# UCC28740DR_Flyback_converter_SCH.net
KiCad netlist of a schematic drawn in Altium Designer
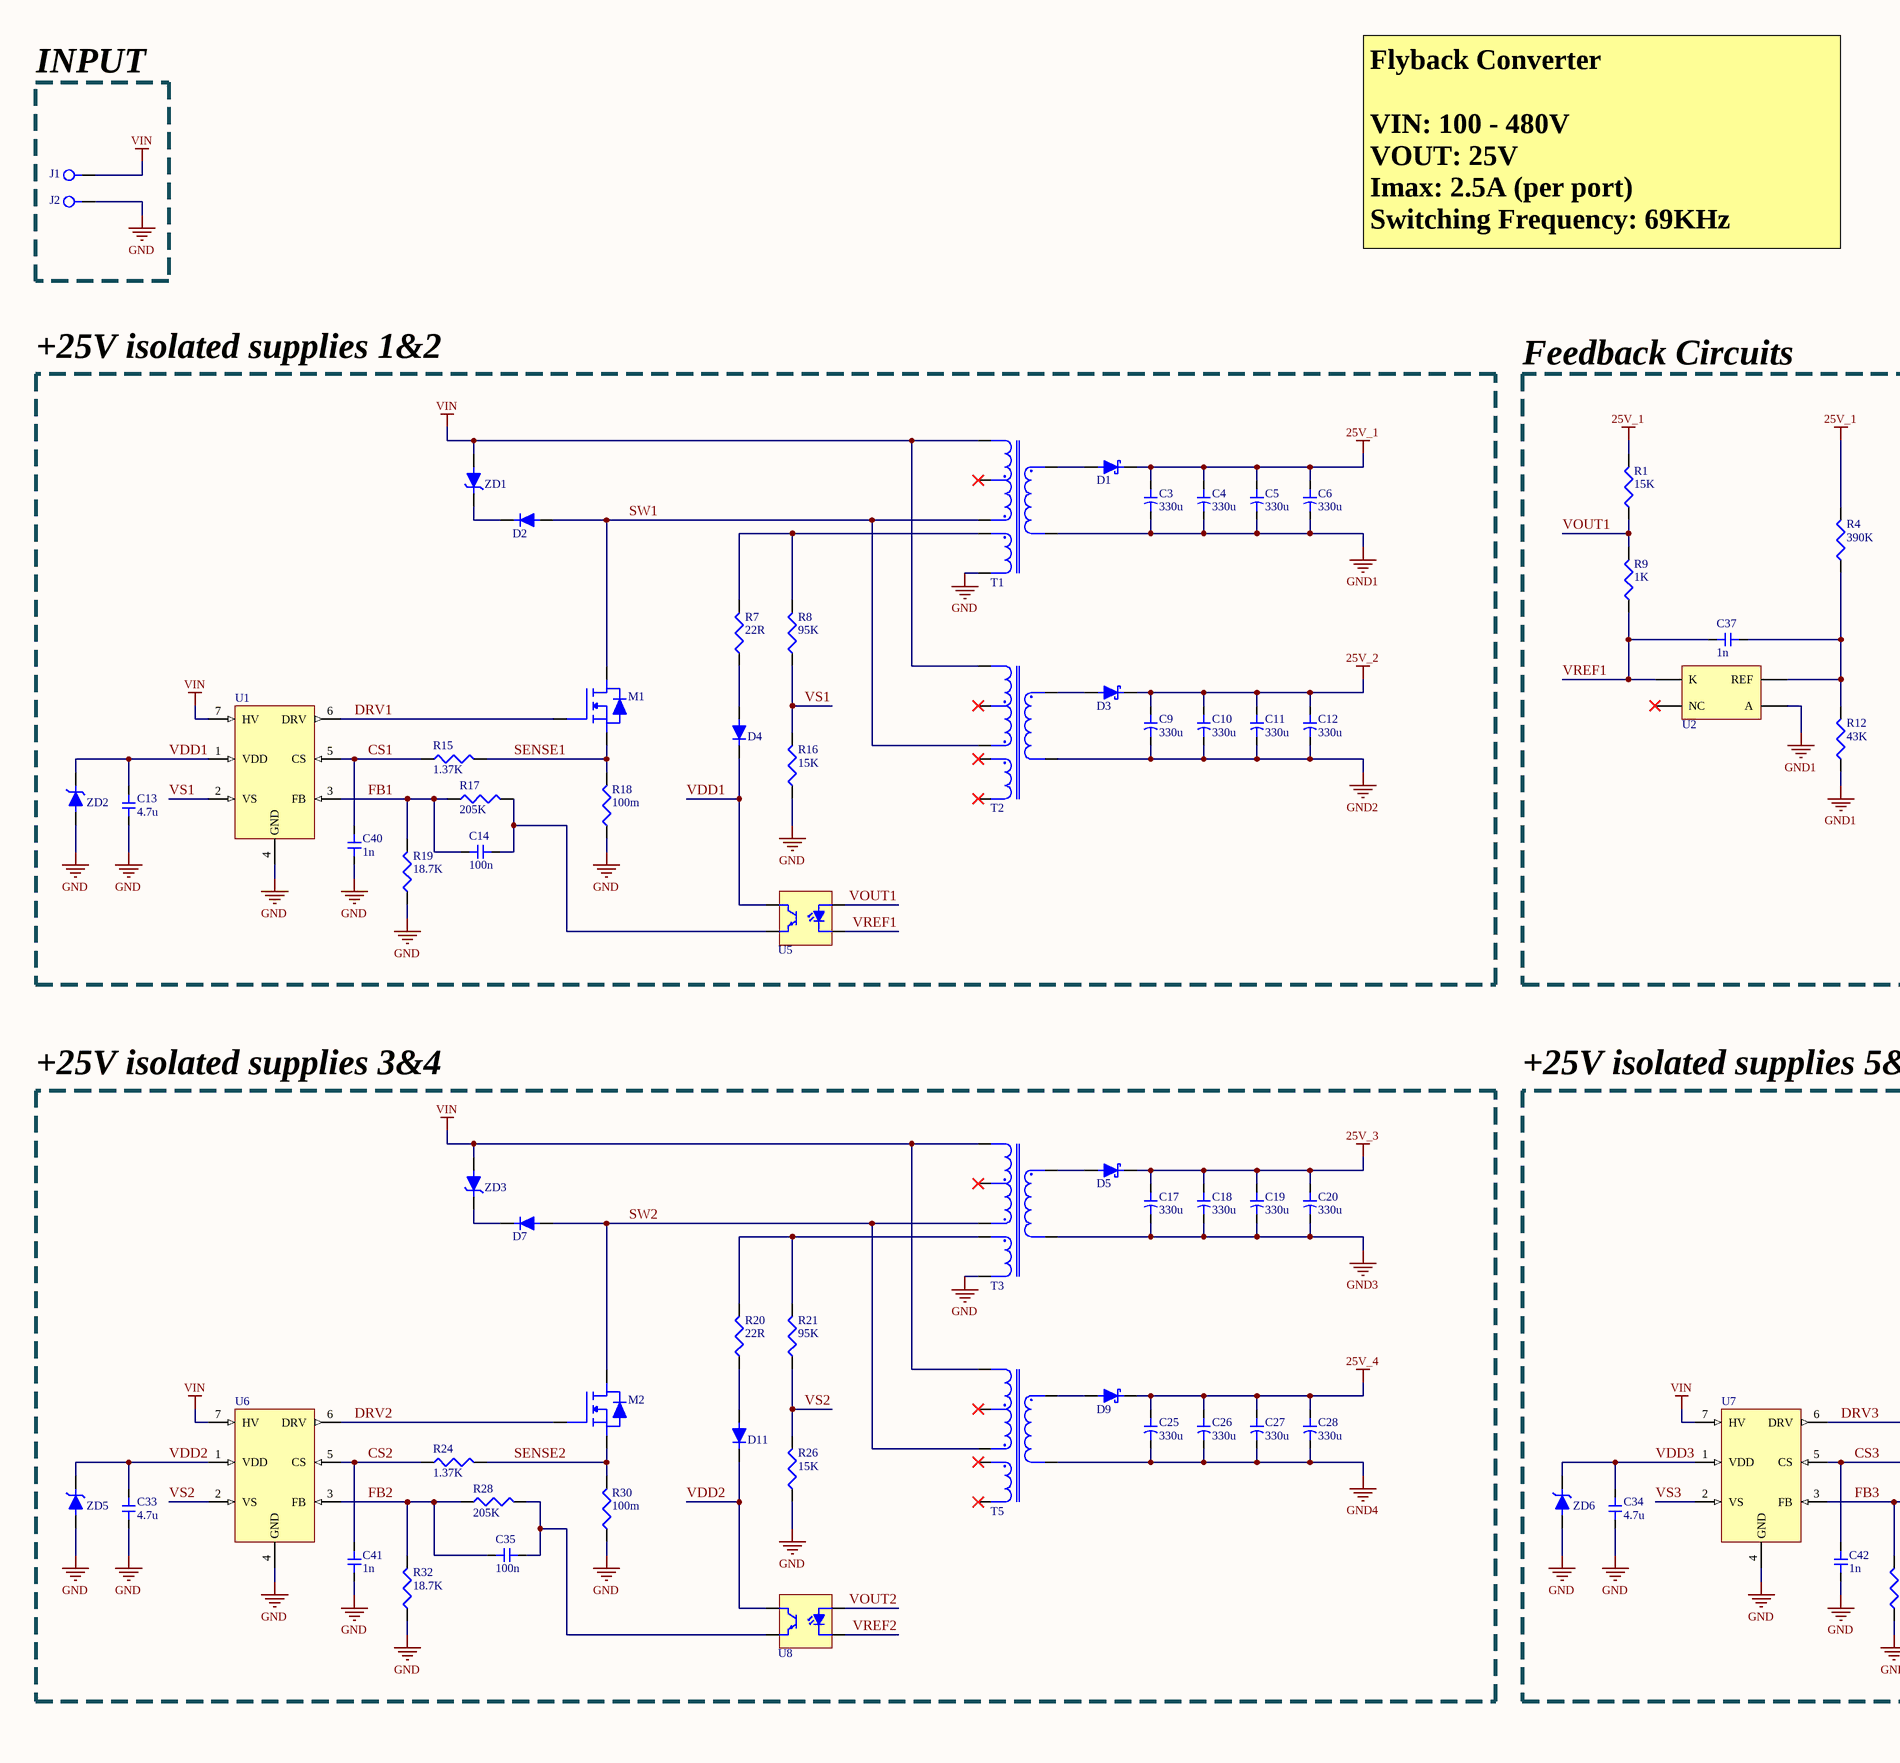
[diagram p0: UCC28740DR Flyback converter SCH.SchDoc, left]
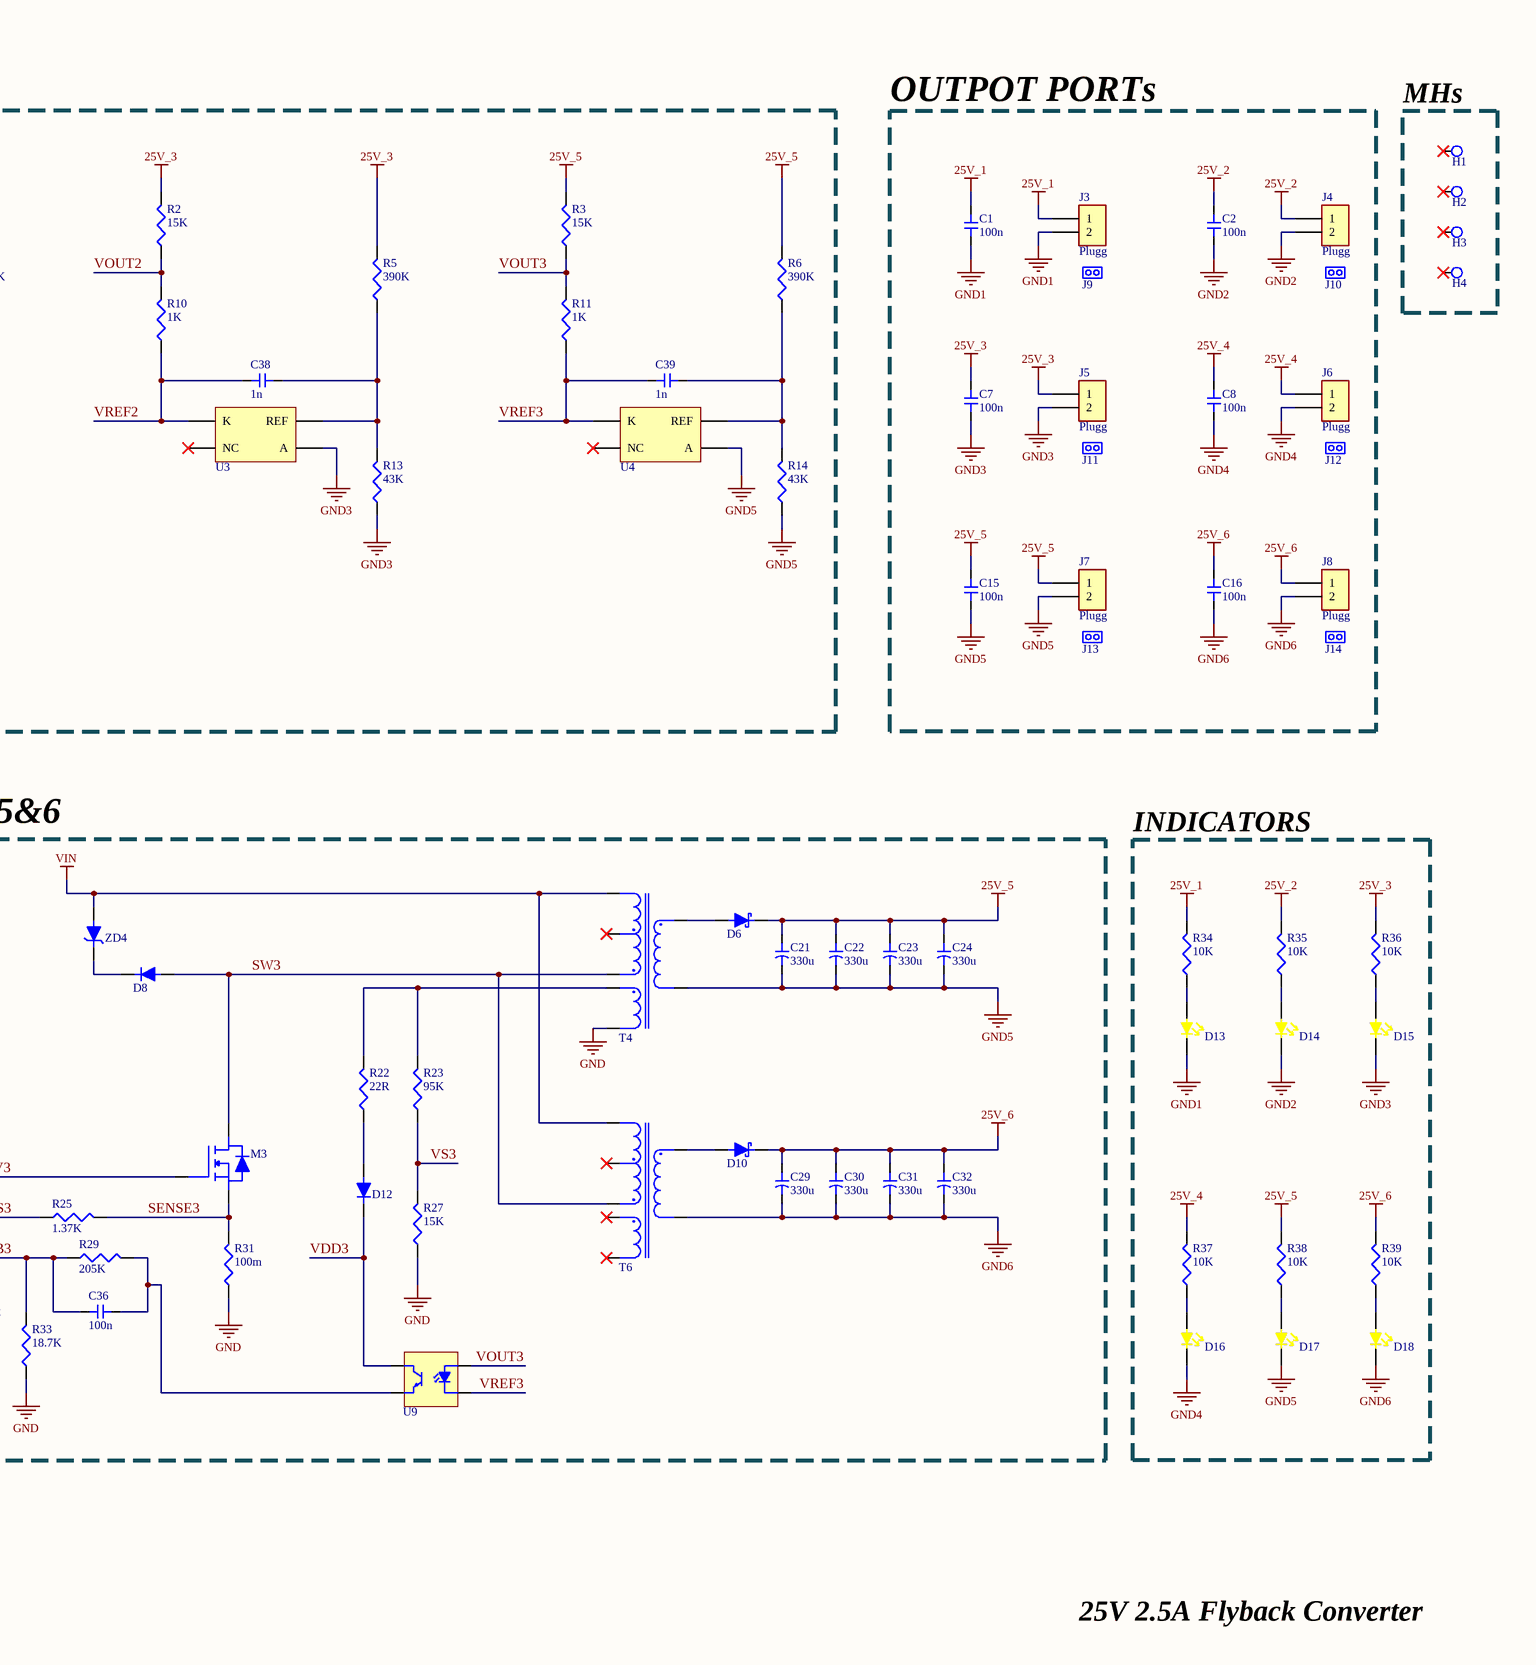
[diagram p1: UCC28740DR Flyback converter SCH.SchDoc, right]

(export (version "E")
  (design (tool "Eeschema 10.0.6"))
  (components
    (comp (ref "C1")
      (value "100n")
      (footprint "0603-CAP")
      (description "50V 100nF X7R ±10% 0603 Multilayer Ceramic Capacitors MLCC - SMD/SMT ROHS")
      (fields (field (name "MANUFACTURER") "YAGEO") (field (name "MFR. PART #") "CC0603KRX7R9BB104"))
      (libsource (lib "Symbols") (part "Cap 100nF"))
    )
    (comp (ref "C2")
      (value "100n")
      (footprint "0603-CAP")
      (description "50V 100nF X7R ±10% 0603 Multilayer Ceramic Capacitors MLCC - SMD/SMT ROHS")
      (fields (field (name "MANUFACTURER") "YAGEO") (field (name "MFR. PART #") "CC0603KRX7R9BB104"))
      (libsource (lib "Symbols") (part "Cap 100nF"))
    )
    (comp (ref "C3")
      (value "330u")
      (footprint "Electrolytic Capacitor D13 P5 H25")
      (description "330uF 100V Plugin,D13xL26mm Aluminum Electrolytic Capacitors - Leaded ROHS")
      (fields (field (name "MANUFACTURER") "HRK") (field (name "MFR. PART #") "CD2883372AM1326VFL"))
      (libsource (lib "Symbols") (part "Electrolytic Cap 330u"))
    )
    (comp (ref "C4")
      (value "330u")
      (footprint "Electrolytic Capacitor D13 P5 H25")
      (description "330uF 100V Plugin,D13xL26mm Aluminum Electrolytic Capacitors - Leaded ROHS")
      (fields (field (name "MANUFACTURER") "HRK") (field (name "MFR. PART #") "CD2883372AM1326VFL"))
      (libsource (lib "Symbols") (part "Electrolytic Cap 330u"))
    )
    (comp (ref "C5")
      (value "330u")
      (footprint "Electrolytic Capacitor D13 P5 H25")
      (description "330uF 100V Plugin,D13xL26mm Aluminum Electrolytic Capacitors - Leaded ROHS")
      (fields (field (name "MANUFACTURER") "HRK") (field (name "MFR. PART #") "CD2883372AM1326VFL"))
      (libsource (lib "Symbols") (part "Electrolytic Cap 330u"))
    )
    (comp (ref "C6")
      (value "330u")
      (footprint "Electrolytic Capacitor D13 P5 H25")
      (description "330uF 100V Plugin,D13xL26mm Aluminum Electrolytic Capacitors - Leaded ROHS")
      (fields (field (name "MANUFACTURER") "HRK") (field (name "MFR. PART #") "CD2883372AM1326VFL"))
      (libsource (lib "Symbols") (part "Electrolytic Cap 330u"))
    )
    (comp (ref "C7")
      (value "100n")
      (footprint "0603-CAP")
      (description "50V 100nF X7R ±10% 0603 Multilayer Ceramic Capacitors MLCC - SMD/SMT ROHS")
      (fields (field (name "MANUFACTURER") "YAGEO") (field (name "MFR. PART #") "CC0603KRX7R9BB104"))
      (libsource (lib "Symbols") (part "Cap 100nF"))
    )
    (comp (ref "C8")
      (value "100n")
      (footprint "0603-CAP")
      (description "50V 100nF X7R ±10% 0603 Multilayer Ceramic Capacitors MLCC - SMD/SMT ROHS")
      (fields (field (name "MANUFACTURER") "YAGEO") (field (name "MFR. PART #") "CC0603KRX7R9BB104"))
      (libsource (lib "Symbols") (part "Cap 100nF"))
    )
    (comp (ref "C9")
      (value "330u")
      (footprint "Electrolytic Capacitor D13 P5 H25")
      (description "330uF 100V Plugin,D13xL26mm Aluminum Electrolytic Capacitors - Leaded ROHS")
      (fields (field (name "MANUFACTURER") "HRK") (field (name "MFR. PART #") "CD2883372AM1326VFL"))
      (libsource (lib "Symbols") (part "Electrolytic Cap 330u"))
    )
    (comp (ref "C10")
      (value "330u")
      (footprint "Electrolytic Capacitor D13 P5 H25")
      (description "330uF 100V Plugin,D13xL26mm Aluminum Electrolytic Capacitors - Leaded ROHS")
      (fields (field (name "MANUFACTURER") "HRK") (field (name "MFR. PART #") "CD2883372AM1326VFL"))
      (libsource (lib "Symbols") (part "Electrolytic Cap 330u"))
    )
    (comp (ref "C11")
      (value "330u")
      (footprint "Electrolytic Capacitor D13 P5 H25")
      (description "330uF 100V Plugin,D13xL26mm Aluminum Electrolytic Capacitors - Leaded ROHS")
      (fields (field (name "MANUFACTURER") "HRK") (field (name "MFR. PART #") "CD2883372AM1326VFL"))
      (libsource (lib "Symbols") (part "Electrolytic Cap 330u"))
    )
    (comp (ref "C12")
      (value "330u")
      (footprint "Electrolytic Capacitor D13 P5 H25")
      (description "330uF 100V Plugin,D13xL26mm Aluminum Electrolytic Capacitors - Leaded ROHS")
      (fields (field (name "MANUFACTURER") "HRK") (field (name "MFR. PART #") "CD2883372AM1326VFL"))
      (libsource (lib "Symbols") (part "Electrolytic Cap 330u"))
    )
    (comp (ref "C13")
      (value "4.7u")
      (footprint "0805-CAP")
      (description "50V 4.7uF X7R ±10% 0805 Multilayer Ceramic Capacitors MLCC - SMD/SMT ROHS")
      (fields
        (field (name "MANUFACTURER") "FH (Guangdong Fenghua Advanced Tech)")
        (field (name "MFR. PART #") "0805B475K500NT")
      )
      (libsource (lib "Symbols") (part "Cap 4.7uF"))
    )
    (comp (ref "C14")
      (value "100n")
      (footprint "0603-CAP")
      (description "50V 100nF X7R ±10% 0603 Multilayer Ceramic Capacitors MLCC - SMD/SMT ROHS")
      (fields (field (name "MANUFACTURER") "YAGEO") (field (name "MFR. PART #") "CC0603KRX7R9BB104"))
      (libsource (lib "Symbols") (part "Cap 100nF"))
    )
    (comp (ref "C15")
      (value "100n")
      (footprint "0603-CAP")
      (description "50V 100nF X7R ±10% 0603 Multilayer Ceramic Capacitors MLCC - SMD/SMT ROHS")
      (fields (field (name "MANUFACTURER") "YAGEO") (field (name "MFR. PART #") "CC0603KRX7R9BB104"))
      (libsource (lib "Symbols") (part "Cap 100nF"))
    )
    (comp (ref "C16")
      (value "100n")
      (footprint "0603-CAP")
      (description "50V 100nF X7R ±10% 0603 Multilayer Ceramic Capacitors MLCC - SMD/SMT ROHS")
      (fields (field (name "MANUFACTURER") "YAGEO") (field (name "MFR. PART #") "CC0603KRX7R9BB104"))
      (libsource (lib "Symbols") (part "Cap 100nF"))
    )
    (comp (ref "C17")
      (value "330u")
      (footprint "Electrolytic Capacitor D13 P5 H25")
      (description "330uF 100V Plugin,D13xL26mm Aluminum Electrolytic Capacitors - Leaded ROHS")
      (fields (field (name "MANUFACTURER") "HRK") (field (name "MFR. PART #") "CD2883372AM1326VFL"))
      (libsource (lib "Symbols") (part "Electrolytic Cap 330u"))
    )
    (comp (ref "C18")
      (value "330u")
      (footprint "Electrolytic Capacitor D13 P5 H25")
      (description "330uF 100V Plugin,D13xL26mm Aluminum Electrolytic Capacitors - Leaded ROHS")
      (fields (field (name "MANUFACTURER") "HRK") (field (name "MFR. PART #") "CD2883372AM1326VFL"))
      (libsource (lib "Symbols") (part "Electrolytic Cap 330u"))
    )
    (comp (ref "C19")
      (value "330u")
      (footprint "Electrolytic Capacitor D13 P5 H25")
      (description "330uF 100V Plugin,D13xL26mm Aluminum Electrolytic Capacitors - Leaded ROHS")
      (fields (field (name "MANUFACTURER") "HRK") (field (name "MFR. PART #") "CD2883372AM1326VFL"))
      (libsource (lib "Symbols") (part "Electrolytic Cap 330u"))
    )
    (comp (ref "C20")
      (value "330u")
      (footprint "Electrolytic Capacitor D13 P5 H25")
      (description "330uF 100V Plugin,D13xL26mm Aluminum Electrolytic Capacitors - Leaded ROHS")
      (fields (field (name "MANUFACTURER") "HRK") (field (name "MFR. PART #") "CD2883372AM1326VFL"))
      (libsource (lib "Symbols") (part "Electrolytic Cap 330u"))
    )
    (comp (ref "C21")
      (value "330u")
      (footprint "Electrolytic Capacitor D13 P5 H25")
      (description "330uF 100V Plugin,D13xL26mm Aluminum Electrolytic Capacitors - Leaded ROHS")
      (fields (field (name "MANUFACTURER") "HRK") (field (name "MFR. PART #") "CD2883372AM1326VFL"))
      (libsource (lib "Symbols") (part "Electrolytic Cap 330u"))
    )
    (comp (ref "C22")
      (value "330u")
      (footprint "Electrolytic Capacitor D13 P5 H25")
      (description "330uF 100V Plugin,D13xL26mm Aluminum Electrolytic Capacitors - Leaded ROHS")
      (fields (field (name "MANUFACTURER") "HRK") (field (name "MFR. PART #") "CD2883372AM1326VFL"))
      (libsource (lib "Symbols") (part "Electrolytic Cap 330u"))
    )
    (comp (ref "C23")
      (value "330u")
      (footprint "Electrolytic Capacitor D13 P5 H25")
      (description "330uF 100V Plugin,D13xL26mm Aluminum Electrolytic Capacitors - Leaded ROHS")
      (fields (field (name "MANUFACTURER") "HRK") (field (name "MFR. PART #") "CD2883372AM1326VFL"))
      (libsource (lib "Symbols") (part "Electrolytic Cap 330u"))
    )
    (comp (ref "C24")
      (value "330u")
      (footprint "Electrolytic Capacitor D13 P5 H25")
      (description "330uF 100V Plugin,D13xL26mm Aluminum Electrolytic Capacitors - Leaded ROHS")
      (fields (field (name "MANUFACTURER") "HRK") (field (name "MFR. PART #") "CD2883372AM1326VFL"))
      (libsource (lib "Symbols") (part "Electrolytic Cap 330u"))
    )
    (comp (ref "C25")
      (value "330u")
      (footprint "Electrolytic Capacitor D13 P5 H25")
      (description "330uF 100V Plugin,D13xL26mm Aluminum Electrolytic Capacitors - Leaded ROHS")
      (fields (field (name "MANUFACTURER") "HRK") (field (name "MFR. PART #") "CD2883372AM1326VFL"))
      (libsource (lib "Symbols") (part "Electrolytic Cap 330u"))
    )
    (comp (ref "C26")
      (value "330u")
      (footprint "Electrolytic Capacitor D13 P5 H25")
      (description "330uF 100V Plugin,D13xL26mm Aluminum Electrolytic Capacitors - Leaded ROHS")
      (fields (field (name "MANUFACTURER") "HRK") (field (name "MFR. PART #") "CD2883372AM1326VFL"))
      (libsource (lib "Symbols") (part "Electrolytic Cap 330u"))
    )
    (comp (ref "C27")
      (value "330u")
      (footprint "Electrolytic Capacitor D13 P5 H25")
      (description "330uF 100V Plugin,D13xL26mm Aluminum Electrolytic Capacitors - Leaded ROHS")
      (fields (field (name "MANUFACTURER") "HRK") (field (name "MFR. PART #") "CD2883372AM1326VFL"))
      (libsource (lib "Symbols") (part "Electrolytic Cap 330u"))
    )
    (comp (ref "C28")
      (value "330u")
      (footprint "Electrolytic Capacitor D13 P5 H25")
      (description "330uF 100V Plugin,D13xL26mm Aluminum Electrolytic Capacitors - Leaded ROHS")
      (fields (field (name "MANUFACTURER") "HRK") (field (name "MFR. PART #") "CD2883372AM1326VFL"))
      (libsource (lib "Symbols") (part "Electrolytic Cap 330u"))
    )
    (comp (ref "C29")
      (value "330u")
      (footprint "Electrolytic Capacitor D13 P5 H25")
      (description "330uF 100V Plugin,D13xL26mm Aluminum Electrolytic Capacitors - Leaded ROHS")
      (fields (field (name "MANUFACTURER") "HRK") (field (name "MFR. PART #") "CD2883372AM1326VFL"))
      (libsource (lib "Symbols") (part "Electrolytic Cap 330u"))
    )
    (comp (ref "C30")
      (value "330u")
      (footprint "Electrolytic Capacitor D13 P5 H25")
      (description "330uF 100V Plugin,D13xL26mm Aluminum Electrolytic Capacitors - Leaded ROHS")
      (fields (field (name "MANUFACTURER") "HRK") (field (name "MFR. PART #") "CD2883372AM1326VFL"))
      (libsource (lib "Symbols") (part "Electrolytic Cap 330u"))
    )
    (comp (ref "C31")
      (value "330u")
      (footprint "Electrolytic Capacitor D13 P5 H25")
      (description "330uF 100V Plugin,D13xL26mm Aluminum Electrolytic Capacitors - Leaded ROHS")
      (fields (field (name "MANUFACTURER") "HRK") (field (name "MFR. PART #") "CD2883372AM1326VFL"))
      (libsource (lib "Symbols") (part "Electrolytic Cap 330u"))
    )
    (comp (ref "C32")
      (value "330u")
      (footprint "Electrolytic Capacitor D13 P5 H25")
      (description "330uF 100V Plugin,D13xL26mm Aluminum Electrolytic Capacitors - Leaded ROHS")
      (fields (field (name "MANUFACTURER") "HRK") (field (name "MFR. PART #") "CD2883372AM1326VFL"))
      (libsource (lib "Symbols") (part "Electrolytic Cap 330u"))
    )
    (comp (ref "C33")
      (value "4.7u")
      (footprint "0805-CAP")
      (description "50V 4.7uF X7R ±10% 0805 Multilayer Ceramic Capacitors MLCC - SMD/SMT ROHS")
      (fields
        (field (name "MANUFACTURER") "FH (Guangdong Fenghua Advanced Tech)")
        (field (name "MFR. PART #") "0805B475K500NT")
      )
      (libsource (lib "Symbols") (part "Cap 4.7uF"))
    )
    (comp (ref "C34")
      (value "4.7u")
      (footprint "0805-CAP")
      (description "50V 4.7uF X7R ±10% 0805 Multilayer Ceramic Capacitors MLCC - SMD/SMT ROHS")
      (fields
        (field (name "MANUFACTURER") "FH (Guangdong Fenghua Advanced Tech)")
        (field (name "MFR. PART #") "0805B475K500NT")
      )
      (libsource (lib "Symbols") (part "Cap 4.7uF"))
    )
    (comp (ref "C35")
      (value "100n")
      (footprint "0603-CAP")
      (description "50V 100nF X7R ±10% 0603 Multilayer Ceramic Capacitors MLCC - SMD/SMT ROHS")
      (fields (field (name "MANUFACTURER") "YAGEO") (field (name "MFR. PART #") "CC0603KRX7R9BB104"))
      (libsource (lib "Symbols") (part "Cap 100nF"))
    )
    (comp (ref "C36")
      (value "100n")
      (footprint "0603-CAP")
      (description "50V 100nF X7R ±10% 0603 Multilayer Ceramic Capacitors MLCC - SMD/SMT ROHS")
      (fields (field (name "MANUFACTURER") "YAGEO") (field (name "MFR. PART #") "CC0603KRX7R9BB104"))
      (libsource (lib "Symbols") (part "Cap 100nF"))
    )
    (comp (ref "C37")
      (value "1n")
      (footprint "0603-CAP")
      (description "50V 1nF X7R ±10% 0603 Multilayer Ceramic Capacitors MLCC - SMD/SMT ROHS")
      (fields (field (name "MANUFACTURER") "YAGEO") (field (name "MFR. PART #") "CC0603KRX7R9BB102"))
      (libsource (lib "Symbols") (part "Cap 1nF"))
    )
    (comp (ref "C38")
      (value "1n")
      (footprint "0603-CAP")
      (description "50V 1nF X7R ±10% 0603 Multilayer Ceramic Capacitors MLCC - SMD/SMT ROHS")
      (fields (field (name "MANUFACTURER") "YAGEO") (field (name "MFR. PART #") "CC0603KRX7R9BB102"))
      (libsource (lib "Symbols") (part "Cap 1nF"))
    )
    (comp (ref "C39")
      (value "1n")
      (footprint "0603-CAP")
      (description "50V 1nF X7R ±10% 0603 Multilayer Ceramic Capacitors MLCC - SMD/SMT ROHS")
      (fields (field (name "MANUFACTURER") "YAGEO") (field (name "MFR. PART #") "CC0603KRX7R9BB102"))
      (libsource (lib "Symbols") (part "Cap 1nF"))
    )
    (comp (ref "C40")
      (value "1n")
      (footprint "0603-CAP")
      (description "50V 1nF X7R ±10% 0603 Multilayer Ceramic Capacitors MLCC - SMD/SMT ROHS")
      (fields (field (name "MANUFACTURER") "YAGEO") (field (name "MFR. PART #") "CC0603KRX7R9BB102"))
      (libsource (lib "Symbols") (part "Cap 1nF"))
    )
    (comp (ref "C41")
      (value "1n")
      (footprint "0603-CAP")
      (description "50V 1nF X7R ±10% 0603 Multilayer Ceramic Capacitors MLCC - SMD/SMT ROHS")
      (fields (field (name "MANUFACTURER") "YAGEO") (field (name "MFR. PART #") "CC0603KRX7R9BB102"))
      (libsource (lib "Symbols") (part "Cap 1nF"))
    )
    (comp (ref "C42")
      (value "1n")
      (footprint "0603-CAP")
      (description "50V 1nF X7R ±10% 0603 Multilayer Ceramic Capacitors MLCC - SMD/SMT ROHS")
      (fields (field (name "MANUFACTURER") "YAGEO") (field (name "MFR. PART #") "CC0603KRX7R9BB102"))
      (libsource (lib "Symbols") (part "Cap 1nF"))
    )
    (comp (ref "D1")
      (value "Schottky Diode")
      (footprint "SMA(DO-214AC)")
      (description "100V Independent Type 850mV@5A 5A SMA(DO-214AC) Schottky Diodes ROHS")
      (fields (field (name "MANUFACTURER") "TWGMC") (field (name "MFR. PART #") "SS510"))
      (libsource (lib "Symbols") (part "Schottky Diode"))
    )
    (comp (ref "D2")
      (value "Fast Diode")
      (footprint "SMC diode")
      (description "1.7V@8A 80ns Independent Type 8A 1kV SMC Fast Recovery / High Efficiency Diodes ROHS")
      (fields
        (field (name "MANUFACTURER") "Shandong Jingdao Microelectronics")
        (field (name "MFR. PART #") "US8MC")
      )
      (libsource (lib "Symbols") (part "Fast Diode"))
    )
    (comp (ref "D3")
      (value "Schottky Diode")
      (footprint "SMA(DO-214AC)")
      (description "100V Independent Type 850mV@5A 5A SMA(DO-214AC) Schottky Diodes ROHS")
      (fields (field (name "MANUFACTURER") "TWGMC") (field (name "MFR. PART #") "SS510"))
      (libsource (lib "Symbols") (part "Schottky Diode"))
    )
    (comp (ref "D4")
      (value "Fast Diode")
      (footprint "SMC diode")
      (description "1.7V@8A 80ns Independent Type 8A 1kV SMC Fast Recovery / High Efficiency Diodes ROHS")
      (fields
        (field (name "MANUFACTURER") "Shandong Jingdao Microelectronics")
        (field (name "MFR. PART #") "US8MC")
      )
      (libsource (lib "Symbols") (part "Fast Diode"))
    )
    (comp (ref "D5")
      (value "Schottky Diode")
      (footprint "SMA(DO-214AC)")
      (description "100V Independent Type 850mV@5A 5A SMA(DO-214AC) Schottky Diodes ROHS")
      (fields (field (name "MANUFACTURER") "TWGMC") (field (name "MFR. PART #") "SS510"))
      (libsource (lib "Symbols") (part "Schottky Diode"))
    )
    (comp (ref "D6")
      (value "Schottky Diode")
      (footprint "SMA(DO-214AC)")
      (description "100V Independent Type 850mV@5A 5A SMA(DO-214AC) Schottky Diodes ROHS")
      (fields (field (name "MANUFACTURER") "TWGMC") (field (name "MFR. PART #") "SS510"))
      (libsource (lib "Symbols") (part "Schottky Diode"))
    )
    (comp (ref "D7")
      (value "Fast Diode")
      (footprint "SMC diode")
      (description "1.7V@8A 80ns Independent Type 8A 1kV SMC Fast Recovery / High Efficiency Diodes ROHS")
      (fields
        (field (name "MANUFACTURER") "Shandong Jingdao Microelectronics")
        (field (name "MFR. PART #") "US8MC")
      )
      (libsource (lib "Symbols") (part "Fast Diode"))
    )
    (comp (ref "D8")
      (value "Fast Diode")
      (footprint "SMC diode")
      (description "1.7V@8A 80ns Independent Type 8A 1kV SMC Fast Recovery / High Efficiency Diodes ROHS")
      (fields
        (field (name "MANUFACTURER") "Shandong Jingdao Microelectronics")
        (field (name "MFR. PART #") "US8MC")
      )
      (libsource (lib "Symbols") (part "Fast Diode"))
    )
    (comp (ref "D9")
      (value "Schottky Diode")
      (footprint "SMA(DO-214AC)")
      (description "100V Independent Type 850mV@5A 5A SMA(DO-214AC) Schottky Diodes ROHS")
      (fields (field (name "MANUFACTURER") "TWGMC") (field (name "MFR. PART #") "SS510"))
      (libsource (lib "Symbols") (part "Schottky Diode"))
    )
    (comp (ref "D10")
      (value "Schottky Diode")
      (footprint "SMA(DO-214AC)")
      (description "100V Independent Type 850mV@5A 5A SMA(DO-214AC) Schottky Diodes ROHS")
      (fields (field (name "MANUFACTURER") "TWGMC") (field (name "MFR. PART #") "SS510"))
      (libsource (lib "Symbols") (part "Schottky Diode"))
    )
    (comp (ref "D11")
      (value "Fast Diode")
      (footprint "SMC diode")
      (description "1.7V@8A 80ns Independent Type 8A 1kV SMC Fast Recovery / High Efficiency Diodes ROHS")
      (fields
        (field (name "MANUFACTURER") "Shandong Jingdao Microelectronics")
        (field (name "MFR. PART #") "US8MC")
      )
      (libsource (lib "Symbols") (part "Fast Diode"))
    )
    (comp (ref "D12")
      (value "Fast Diode")
      (footprint "SMC diode")
      (description "1.7V@8A 80ns Independent Type 8A 1kV SMC Fast Recovery / High Efficiency Diodes ROHS")
      (fields
        (field (name "MANUFACTURER") "Shandong Jingdao Microelectronics")
        (field (name "MFR. PART #") "US8MC")
      )
      (libsource (lib "Symbols") (part "Fast Diode"))
    )
    (comp (ref "D13")
      (value "Yellow LED")
      (footprint "yellow led")
      (description "2-Yellow lens-30℃~+85℃ Positive post White 120° 80mW 0805 Light Emitting Diodes (LED) ROHS")
      (fields (field (name "MANUFACTURER") "XINGLIGHT") (field (name "MFR. PART #") "XL-2012UWC"))
      (libsource (lib "Symbols") (part "Yellow LED"))
    )
    (comp (ref "D14")
      (value "Yellow LED")
      (footprint "yellow led")
      (description "2-Yellow lens-30℃~+85℃ Positive post White 120° 80mW 0805 Light Emitting Diodes (LED) ROHS")
      (fields (field (name "MANUFACTURER") "XINGLIGHT") (field (name "MFR. PART #") "XL-2012UWC"))
      (libsource (lib "Symbols") (part "Yellow LED"))
    )
    (comp (ref "D15")
      (value "Yellow LED")
      (footprint "yellow led")
      (description "2-Yellow lens-30℃~+85℃ Positive post White 120° 80mW 0805 Light Emitting Diodes (LED) ROHS")
      (fields (field (name "MANUFACTURER") "XINGLIGHT") (field (name "MFR. PART #") "XL-2012UWC"))
      (libsource (lib "Symbols") (part "Yellow LED"))
    )
    (comp (ref "D16")
      (value "Yellow LED")
      (footprint "yellow led")
      (description "2-Yellow lens-30℃~+85℃ Positive post White 120° 80mW 0805 Light Emitting Diodes (LED) ROHS")
      (fields (field (name "MANUFACTURER") "XINGLIGHT") (field (name "MFR. PART #") "XL-2012UWC"))
      (libsource (lib "Symbols") (part "Yellow LED"))
    )
    (comp (ref "D17")
      (value "Yellow LED")
      (footprint "yellow led")
      (description "2-Yellow lens-30℃~+85℃ Positive post White 120° 80mW 0805 Light Emitting Diodes (LED) ROHS")
      (fields (field (name "MANUFACTURER") "XINGLIGHT") (field (name "MFR. PART #") "XL-2012UWC"))
      (libsource (lib "Symbols") (part "Yellow LED"))
    )
    (comp (ref "D18")
      (value "Yellow LED")
      (footprint "yellow led")
      (description "2-Yellow lens-30℃~+85℃ Positive post White 120° 80mW 0805 Light Emitting Diodes (LED) ROHS")
      (fields (field (name "MANUFACTURER") "XINGLIGHT") (field (name "MFR. PART #") "XL-2012UWC"))
      (libsource (lib "Symbols") (part "Yellow LED"))
    )
    (comp (ref "H1")
      (value "Mounting hole")
      (footprint "Monting Hole")
      (libsource (lib "Symbols") (part "Mounting hole"))
    )
    (comp (ref "H2")
      (value "Mounting hole")
      (footprint "Monting Hole")
      (libsource (lib "Symbols") (part "Mounting hole"))
    )
    (comp (ref "H3")
      (value "Mounting hole")
      (footprint "Monting Hole")
      (libsource (lib "Symbols") (part "Mounting hole"))
    )
    (comp (ref "H4")
      (value "Mounting hole")
      (footprint "Monting Hole")
      (libsource (lib "Symbols") (part "Mounting hole"))
    )
    (comp (ref "J1")
      (value "Banana Connector Red")
      (footprint "Bannana Connector Red")
      (description "Terminal Red Banana Connectors / Alligator Clips ROHS")
      (fields (field (name "MANUFACTURER") "Changzhou Amass Elec") (field (name "MFR. PART #") "24.247.1"))
      (libsource (lib "Symbols") (part "Banana Connector Red"))
    )
    (comp (ref "J2")
      (value "Banana Connector Black")
      (footprint "Bannana Connector Black")
      (description "Terminal Black Banana Connectors / Alligator Clips ROHS")
      (fields (field (name "MANUFACTURER") "Changzhou Amass Elec") (field (name "MFR. PART #") "24.247.2"))
      (libsource (lib "Symbols") (part "Banana Connector Black"))
    )
    (comp (ref "J3")
      (value "Plugg")
      (footprint "Pluggable Terminal Block 2")
      (fields
        (field (name "MFR. PART #") "WJ2EDGR-5.08-2P")
        (field (name "MANUFACTURER") "Ningbo Kangnex Elec")
      )
      (libsource (lib "Symbols") (part "Pluggable Rozzeta 2P"))
    )
    (comp (ref "J4")
      (value "Plugg")
      (footprint "Pluggable Terminal Block 2")
      (fields
        (field (name "MFR. PART #") "WJ2EDGR-5.08-2P")
        (field (name "MANUFACTURER") "Ningbo Kangnex Elec")
      )
      (libsource (lib "Symbols") (part "Pluggable Rozzeta 2P"))
    )
    (comp (ref "J5")
      (value "Plugg")
      (footprint "Pluggable Terminal Block 2")
      (fields
        (field (name "MFR. PART #") "WJ2EDGR-5.08-2P")
        (field (name "MANUFACTURER") "Ningbo Kangnex Elec")
      )
      (libsource (lib "Symbols") (part "Pluggable Rozzeta 2P"))
    )
    (comp (ref "J6")
      (value "Plugg")
      (footprint "Pluggable Terminal Block 2")
      (fields
        (field (name "MFR. PART #") "WJ2EDGR-5.08-2P")
        (field (name "MANUFACTURER") "Ningbo Kangnex Elec")
      )
      (libsource (lib "Symbols") (part "Pluggable Rozzeta 2P"))
    )
    (comp (ref "J7")
      (value "Plugg")
      (footprint "Pluggable Terminal Block 2")
      (fields
        (field (name "MFR. PART #") "WJ2EDGR-5.08-2P")
        (field (name "MANUFACTURER") "Ningbo Kangnex Elec")
      )
      (libsource (lib "Symbols") (part "Pluggable Rozzeta 2P"))
    )
    (comp (ref "J8")
      (value "Plugg")
      (footprint "Pluggable Terminal Block 2")
      (fields
        (field (name "MFR. PART #") "WJ2EDGR-5.08-2P")
        (field (name "MANUFACTURER") "Ningbo Kangnex Elec")
      )
      (libsource (lib "Symbols") (part "Pluggable Rozzeta 2P"))
    )
    (comp (ref "J9")
      (value "Pluggable Rozzeta 2P female")
      (fields
        (field (name "MFR. PART #") "WJ2EDGK-5.08-2P")
        (field (name "MANUFACTURER") "Ningbo Kangnex Elec")
      )
      (libsource (lib "Symbols") (part "Pluggable Rozzeta 2P female"))
    )
    (comp (ref "J10")
      (value "Pluggable Rozzeta 2P female")
      (fields
        (field (name "MFR. PART #") "WJ2EDGK-5.08-2P")
        (field (name "MANUFACTURER") "Ningbo Kangnex Elec")
      )
      (libsource (lib "Symbols") (part "Pluggable Rozzeta 2P female"))
    )
    (comp (ref "J11")
      (value "Pluggable Rozzeta 2P female")
      (fields
        (field (name "MFR. PART #") "WJ2EDGK-5.08-2P")
        (field (name "MANUFACTURER") "Ningbo Kangnex Elec")
      )
      (libsource (lib "Symbols") (part "Pluggable Rozzeta 2P female"))
    )
    (comp (ref "J12")
      (value "Pluggable Rozzeta 2P female")
      (fields
        (field (name "MFR. PART #") "WJ2EDGK-5.08-2P")
        (field (name "MANUFACTURER") "Ningbo Kangnex Elec")
      )
      (libsource (lib "Symbols") (part "Pluggable Rozzeta 2P female"))
    )
    (comp (ref "J13")
      (value "Pluggable Rozzeta 2P female")
      (fields
        (field (name "MFR. PART #") "WJ2EDGK-5.08-2P")
        (field (name "MANUFACTURER") "Ningbo Kangnex Elec")
      )
      (libsource (lib "Symbols") (part "Pluggable Rozzeta 2P female"))
    )
    (comp (ref "J14")
      (value "Pluggable Rozzeta 2P female")
      (fields
        (field (name "MFR. PART #") "WJ2EDGK-5.08-2P")
        (field (name "MANUFACTURER") "Ningbo Kangnex Elec")
      )
      (libsource (lib "Symbols") (part "Pluggable Rozzeta 2P female"))
    )
    (comp (ref "M1")
      (value "650V 20A MOSFET")
      (footprint "TO-263")
      (description "650V 20A 190mΩ 126W 3.5V TO-263 MOSFETs ROHS")
      (fields (field (name "MANUFACTURER") "ANHI") (field (name "MFR. PART #") "ASB65R220E"))
      (libsource (lib "Symbols") (part "650V 20A MOSFET"))
    )
    (comp (ref "M2")
      (value "650V 20A MOSFET")
      (footprint "TO-263")
      (description "650V 20A 190mΩ 126W 3.5V TO-263 MOSFETs ROHS")
      (fields (field (name "MANUFACTURER") "ANHI") (field (name "MFR. PART #") "ASB65R220E"))
      (libsource (lib "Symbols") (part "650V 20A MOSFET"))
    )
    (comp (ref "M3")
      (value "650V 20A MOSFET")
      (footprint "TO-263")
      (description "650V 20A 190mΩ 126W 3.5V TO-263 MOSFETs ROHS")
      (fields (field (name "MANUFACTURER") "ANHI") (field (name "MFR. PART #") "ASB65R220E"))
      (libsource (lib "Symbols") (part "650V 20A MOSFET"))
    )
    (comp (ref "R1")
      (value "15K")
      (footprint "0603-RES")
      (description "100mW Thick Film Resistors 75V ±100ppm/℃ ±1% 15kΩ 0603 Chip Resistor - Surface Mount ROHS")
      (fields (field (name "MANUFACTURER") "FOJAN") (field (name "MFR. PART #") "FRC0603F1502TS"))
      (libsource (lib "Symbols") (part "Resistor 15K"))
    )
    (comp (ref "R2")
      (value "15K")
      (footprint "0603-RES")
      (description "100mW Thick Film Resistors 75V ±100ppm/℃ ±1% 15kΩ 0603 Chip Resistor - Surface Mount ROHS")
      (fields (field (name "MANUFACTURER") "FOJAN") (field (name "MFR. PART #") "FRC0603F1502TS"))
      (libsource (lib "Symbols") (part "Resistor 15K"))
    )
    (comp (ref "R3")
      (value "15K")
      (footprint "0603-RES")
      (description "100mW Thick Film Resistors 75V ±100ppm/℃ ±1% 15kΩ 0603 Chip Resistor - Surface Mount ROHS")
      (fields (field (name "MANUFACTURER") "FOJAN") (field (name "MFR. PART #") "FRC0603F1502TS"))
      (libsource (lib "Symbols") (part "Resistor 15K"))
    )
    (comp (ref "R4")
      (value "390K")
      (footprint "0603-RES")
      (description "100mW Thick Film Resistors 75V ±100ppm/℃ ±5% 390kΩ 0603 Chip Resistor - Surface Mount ROHS")
      (fields (field (name "MANUFACTURER") "FOJAN") (field (name "MFR. PART #") "FRC0603J394 TS"))
      (libsource (lib "Symbols") (part "Resistor 390K"))
    )
    (comp (ref "R5")
      (value "390K")
      (footprint "0603-RES")
      (description "100mW Thick Film Resistors 75V ±100ppm/℃ ±5% 390kΩ 0603 Chip Resistor - Surface Mount ROHS")
      (fields (field (name "MANUFACTURER") "FOJAN") (field (name "MFR. PART #") "FRC0603J394 TS"))
      (libsource (lib "Symbols") (part "Resistor 390K"))
    )
    (comp (ref "R6")
      (value "390K")
      (footprint "0603-RES")
      (description "100mW Thick Film Resistors 75V ±100ppm/℃ ±5% 390kΩ 0603 Chip Resistor - Surface Mount ROHS")
      (fields (field (name "MANUFACTURER") "FOJAN") (field (name "MFR. PART #") "FRC0603J394 TS"))
      (libsource (lib "Symbols") (part "Resistor 390K"))
    )
    (comp (ref "R7")
      (value "22R")
      (footprint "0603-RES")
      (description "100mW Thick Film Resistors 75V ±100ppm/℃ ±5% 22Ω 0603 Chip Resistor - Surface Mount ROHS")
      (fields (field (name "MANUFACTURER") "FOJAN") (field (name "MFR. PART #") "FRC0603J220 TS"))
      (libsource (lib "Symbols") (part "Resistor 22R"))
    )
    (comp (ref "R8")
      (value "95K")
      (footprint "0603-RES")
      (description "100mW Thick Film Resistors 75V ±100ppm/℃ ±1% 95.3kΩ 0603 Chip Resistor - Surface Mount ROHSFOJAN")
      (fields (field (name "MANUFACTURER") "FOJAN") (field (name "MFR. PART #") "FRC0603F9532TS"))
      (libsource (lib "Symbols") (part "Resistor 95K"))
    )
    (comp (ref "R9")
      (value "1K")
      (footprint "0603-RES")
      (description "100mW Thick Film Resistors 75V ±100ppm/℃ ±5% 1kΩ 0603 Chip Resistor - Surface Mount ROHS")
      (fields (field (name "MANUFACTURER") "FOJAN") (field (name "MFR. PART #") "FRC0603J102 TS"))
      (libsource (lib "Symbols") (part "Resistor 1K"))
    )
    (comp (ref "R10")
      (value "1K")
      (footprint "0603-RES")
      (description "100mW Thick Film Resistors 75V ±100ppm/℃ ±5% 1kΩ 0603 Chip Resistor - Surface Mount ROHS")
      (fields (field (name "MANUFACTURER") "FOJAN") (field (name "MFR. PART #") "FRC0603J102 TS"))
      (libsource (lib "Symbols") (part "Resistor 1K"))
    )
    (comp (ref "R11")
      (value "1K")
      (footprint "0603-RES")
      (description "100mW Thick Film Resistors 75V ±100ppm/℃ ±5% 1kΩ 0603 Chip Resistor - Surface Mount ROHS")
      (fields (field (name "MANUFACTURER") "FOJAN") (field (name "MFR. PART #") "FRC0603J102 TS"))
      (libsource (lib "Symbols") (part "Resistor 1K"))
    )
    (comp (ref "R12")
      (value "43K")
      (footprint "0603-RES")
      (description "100mW Thick Film Resistors 75V ±100ppm/℃ ±1% 43kΩ 0603 Chip Resistor - Surface Mount ROHS")
      (fields (field (name "MANUFACTURER") "FOJAN") (field (name "MFR. PART #") "FRC0603F4302TS"))
      (libsource (lib "Symbols") (part "Resistor 43K"))
    )
    (comp (ref "R13")
      (value "43K")
      (footprint "0603-RES")
      (description "100mW Thick Film Resistors 75V ±100ppm/℃ ±1% 43kΩ 0603 Chip Resistor - Surface Mount ROHS")
      (fields (field (name "MANUFACTURER") "FOJAN") (field (name "MFR. PART #") "FRC0603F4302TS"))
      (libsource (lib "Symbols") (part "Resistor 43K"))
    )
    (comp (ref "R14")
      (value "43K")
      (footprint "0603-RES")
      (description "100mW Thick Film Resistors 75V ±100ppm/℃ ±1% 43kΩ 0603 Chip Resistor - Surface Mount ROHS")
      (fields (field (name "MANUFACTURER") "FOJAN") (field (name "MFR. PART #") "FRC0603F4302TS"))
      (libsource (lib "Symbols") (part "Resistor 43K"))
    )
    (comp (ref "R15")
      (value "1.37K")
      (footprint "0603-RES")
      (description "100mW Thick Film Resistors 75V ±100ppm/℃ ±1% 1.37kΩ 0603 Chip Resistor - Surface Mount ROHS")
      (fields (field (name "MANUFACTURER") "FOJAN") (field (name "MFR. PART #") "FRC0603F1371TS"))
      (libsource (lib "Symbols") (part "Resistor 1.37K"))
    )
    (comp (ref "R16")
      (value "15K")
      (footprint "0603-RES")
      (description "100mW Thick Film Resistors 75V ±100ppm/℃ ±1% 15kΩ 0603 Chip Resistor - Surface Mount ROHS")
      (fields (field (name "MANUFACTURER") "FOJAN") (field (name "MFR. PART #") "FRC0603F1502TS"))
      (libsource (lib "Symbols") (part "Resistor 15K"))
    )
    (comp (ref "R17")
      (value "205K")
      (footprint "0603-RES")
      (description "100mW Thick Film Resistors 75V ±100ppm/℃ ±1% 205kΩ 0603 Chip Resistor - Surface Mount ROHS")
      (fields (field (name "MANUFACTURER") "FOJAN") (field (name "MFR. PART #") "FRC0603F2053TS"))
      (libsource (lib "Symbols") (part "Resistor 205K"))
    )
    (comp (ref "R18")
      (value "100m")
      (footprint "0603-RES")
      (description "100mW Thick Film Resistors 75V ±800ppm/℃ ±1% 140mΩ 0603 Chip Resistor - Surface Mount ROHS")
      (fields
        (field (name "MANUFACTURER") "UNI-ROYAL(Uniroyal Elec)")
        (field (name "MFR. PART #") "0603WAJ010KT5E")
      )
      (libsource (lib "Symbols") (part "Resistor 100mohm"))
    )
    (comp (ref "R19")
      (value "18.7K")
      (footprint "0603-RES")
      (description "100mW Thick Film Resistors 75V ±100ppm/℃ ±1% 18.7kΩ 0603 Chip Resistor - Surface Mount ROHS")
      (fields (field (name "MANUFACTURER") "YAGEO") (field (name "MFR. PART #") "RC0603FR-0718K7L"))
      (libsource (lib "Symbols") (part "Resistor 18.7K"))
    )
    (comp (ref "R20")
      (value "22R")
      (footprint "0603-RES")
      (description "100mW Thick Film Resistors 75V ±100ppm/℃ ±5% 22Ω 0603 Chip Resistor - Surface Mount ROHS")
      (fields (field (name "MANUFACTURER") "FOJAN") (field (name "MFR. PART #") "FRC0603J220 TS"))
      (libsource (lib "Symbols") (part "Resistor 22R"))
    )
    (comp (ref "R21")
      (value "95K")
      (footprint "0603-RES")
      (description "100mW Thick Film Resistors 75V ±100ppm/℃ ±1% 95.3kΩ 0603 Chip Resistor - Surface Mount ROHSFOJAN")
      (fields (field (name "MANUFACTURER") "FOJAN") (field (name "MFR. PART #") "FRC0603F9532TS"))
      (libsource (lib "Symbols") (part "Resistor 95K"))
    )
    (comp (ref "R22")
      (value "22R")
      (footprint "0603-RES")
      (description "100mW Thick Film Resistors 75V ±100ppm/℃ ±5% 22Ω 0603 Chip Resistor - Surface Mount ROHS")
      (fields (field (name "MANUFACTURER") "FOJAN") (field (name "MFR. PART #") "FRC0603J220 TS"))
      (libsource (lib "Symbols") (part "Resistor 22R"))
    )
    (comp (ref "R23")
      (value "95K")
      (footprint "0603-RES")
      (description "100mW Thick Film Resistors 75V ±100ppm/℃ ±1% 95.3kΩ 0603 Chip Resistor - Surface Mount ROHSFOJAN")
      (fields (field (name "MANUFACTURER") "FOJAN") (field (name "MFR. PART #") "FRC0603F9532TS"))
      (libsource (lib "Symbols") (part "Resistor 95K"))
    )
    (comp (ref "R24")
      (value "1.37K")
      (footprint "0603-RES")
      (description "100mW Thick Film Resistors 75V ±100ppm/℃ ±1% 1.37kΩ 0603 Chip Resistor - Surface Mount ROHS")
      (fields (field (name "MANUFACTURER") "FOJAN") (field (name "MFR. PART #") "FRC0603F1371TS"))
      (libsource (lib "Symbols") (part "Resistor 1.37K"))
    )
    (comp (ref "R25")
      (value "1.37K")
      (footprint "0603-RES")
      (description "100mW Thick Film Resistors 75V ±100ppm/℃ ±1% 1.37kΩ 0603 Chip Resistor - Surface Mount ROHS")
      (fields (field (name "MANUFACTURER") "FOJAN") (field (name "MFR. PART #") "FRC0603F1371TS"))
      (libsource (lib "Symbols") (part "Resistor 1.37K"))
    )
    (comp (ref "R26")
      (value "15K")
      (footprint "0603-RES")
      (description "100mW Thick Film Resistors 75V ±100ppm/℃ ±1% 15kΩ 0603 Chip Resistor - Surface Mount ROHS")
      (fields (field (name "MANUFACTURER") "FOJAN") (field (name "MFR. PART #") "FRC0603F1502TS"))
      (libsource (lib "Symbols") (part "Resistor 15K"))
    )
    (comp (ref "R27")
      (value "15K")
      (footprint "0603-RES")
      (description "100mW Thick Film Resistors 75V ±100ppm/℃ ±1% 15kΩ 0603 Chip Resistor - Surface Mount ROHS")
      (fields (field (name "MANUFACTURER") "FOJAN") (field (name "MFR. PART #") "FRC0603F1502TS"))
      (libsource (lib "Symbols") (part "Resistor 15K"))
    )
    (comp (ref "R28")
      (value "205K")
      (footprint "0603-RES")
      (description "100mW Thick Film Resistors 75V ±100ppm/℃ ±1% 205kΩ 0603 Chip Resistor - Surface Mount ROHS")
      (fields (field (name "MANUFACTURER") "FOJAN") (field (name "MFR. PART #") "FRC0603F2053TS"))
      (libsource (lib "Symbols") (part "Resistor 205K"))
    )
    (comp (ref "R29")
      (value "205K")
      (footprint "0603-RES")
      (description "100mW Thick Film Resistors 75V ±100ppm/℃ ±1% 205kΩ 0603 Chip Resistor - Surface Mount ROHS")
      (fields (field (name "MANUFACTURER") "FOJAN") (field (name "MFR. PART #") "FRC0603F2053TS"))
      (libsource (lib "Symbols") (part "Resistor 205K"))
    )
    (comp (ref "R30")
      (value "100m")
      (footprint "0603-RES")
      (description "100mW Thick Film Resistors 75V ±800ppm/℃ ±1% 140mΩ 0603 Chip Resistor - Surface Mount ROHS")
      (fields
        (field (name "MANUFACTURER") "UNI-ROYAL(Uniroyal Elec)")
        (field (name "MFR. PART #") "0603WAJ010KT5E")
      )
      (libsource (lib "Symbols") (part "Resistor 100mohm"))
    )
    (comp (ref "R31")
      (value "100m")
      (footprint "0603-RES")
      (description "100mW Thick Film Resistors 75V ±800ppm/℃ ±1% 140mΩ 0603 Chip Resistor - Surface Mount ROHS")
      (fields
        (field (name "MANUFACTURER") "UNI-ROYAL(Uniroyal Elec)")
        (field (name "MFR. PART #") "0603WAJ010KT5E")
      )
      (libsource (lib "Symbols") (part "Resistor 100mohm"))
    )
    (comp (ref "R32")
      (value "18.7K")
      (footprint "0603-RES")
      (description "100mW Thick Film Resistors 75V ±100ppm/℃ ±1% 18.7kΩ 0603 Chip Resistor - Surface Mount ROHS")
      (fields (field (name "MANUFACTURER") "YAGEO") (field (name "MFR. PART #") "RC0603FR-0718K7L"))
      (libsource (lib "Symbols") (part "Resistor 18.7K"))
    )
    (comp (ref "R33")
      (value "18.7K")
      (footprint "0603-RES")
      (description "100mW Thick Film Resistors 75V ±100ppm/℃ ±1% 18.7kΩ 0603 Chip Resistor - Surface Mount ROHS")
      (fields (field (name "MANUFACTURER") "YAGEO") (field (name "MFR. PART #") "RC0603FR-0718K7L"))
      (libsource (lib "Symbols") (part "Resistor 18.7K"))
    )
    (comp (ref "R34")
      (value "10K")
      (footprint "0603-RES")
      (description "100mW Thick Film Resistors 75V ±100ppm/℃ ±1% 10kΩ 0603 Chip Resistor - Surface Mount ROHS")
      (fields
        (field (name "MANUFACTURER") "UNI-ROYAL(Uniroyal Elec)")
        (field (name "MFR. PART #") "0603WAF1002T5E")
      )
      (libsource (lib "Symbols") (part "Resistor 10K"))
    )
    (comp (ref "R35")
      (value "10K")
      (footprint "0603-RES")
      (description "100mW Thick Film Resistors 75V ±100ppm/℃ ±1% 10kΩ 0603 Chip Resistor - Surface Mount ROHS")
      (fields
        (field (name "MANUFACTURER") "UNI-ROYAL(Uniroyal Elec)")
        (field (name "MFR. PART #") "0603WAF1002T5E")
      )
      (libsource (lib "Symbols") (part "Resistor 10K"))
    )
    (comp (ref "R36")
      (value "10K")
      (footprint "0603-RES")
      (description "100mW Thick Film Resistors 75V ±100ppm/℃ ±1% 10kΩ 0603 Chip Resistor - Surface Mount ROHS")
      (fields
        (field (name "MANUFACTURER") "UNI-ROYAL(Uniroyal Elec)")
        (field (name "MFR. PART #") "0603WAF1002T5E")
      )
      (libsource (lib "Symbols") (part "Resistor 10K"))
    )
    (comp (ref "R37")
      (value "10K")
      (footprint "0603-RES")
      (description "100mW Thick Film Resistors 75V ±100ppm/℃ ±1% 10kΩ 0603 Chip Resistor - Surface Mount ROHS")
      (fields
        (field (name "MANUFACTURER") "UNI-ROYAL(Uniroyal Elec)")
        (field (name "MFR. PART #") "0603WAF1002T5E")
      )
      (libsource (lib "Symbols") (part "Resistor 10K"))
    )
    (comp (ref "R38")
      (value "10K")
      (footprint "0603-RES")
      (description "100mW Thick Film Resistors 75V ±100ppm/℃ ±1% 10kΩ 0603 Chip Resistor - Surface Mount ROHS")
      (fields
        (field (name "MANUFACTURER") "UNI-ROYAL(Uniroyal Elec)")
        (field (name "MFR. PART #") "0603WAF1002T5E")
      )
      (libsource (lib "Symbols") (part "Resistor 10K"))
    )
    (comp (ref "R39")
      (value "10K")
      (footprint "0603-RES")
      (description "100mW Thick Film Resistors 75V ±100ppm/℃ ±1% 10kΩ 0603 Chip Resistor - Surface Mount ROHS")
      (fields
        (field (name "MANUFACTURER") "UNI-ROYAL(Uniroyal Elec)")
        (field (name "MFR. PART #") "0603WAF1002T5E")
      )
      (libsource (lib "Symbols") (part "Resistor 10K"))
    )
    (comp (ref "T1")
      (value "750343068")
      (footprint "29.2x30.35 Transformer")
      (description "Power Transformers MID-OLTI UCC28740 230 uH 60 W")
      (fields (field (name "MANUFACTURER") "Wurth Elektronik"))
      (libsource (lib "Symbols") (part "Switching Transformer"))
    )
    (comp (ref "T2")
      (value "750343068")
      (footprint "29.2x30.35 Transformer")
      (description "Power Transformers MID-OLTI UCC28740 230 uH 60 W")
      (fields (field (name "MANUFACTURER") "Wurth Elektronik"))
      (libsource (lib "Symbols") (part "Switching Transformer"))
    )
    (comp (ref "T3")
      (value "750343068")
      (footprint "29.2x30.35 Transformer")
      (description "Power Transformers MID-OLTI UCC28740 230 uH 60 W")
      (fields (field (name "MANUFACTURER") "Wurth Elektronik"))
      (libsource (lib "Symbols") (part "Switching Transformer"))
    )
    (comp (ref "T4")
      (value "750343068")
      (footprint "29.2x30.35 Transformer")
      (description "Power Transformers MID-OLTI UCC28740 230 uH 60 W")
      (fields (field (name "MANUFACTURER") "Wurth Elektronik"))
      (libsource (lib "Symbols") (part "Switching Transformer"))
    )
    (comp (ref "T5")
      (value "750343068")
      (footprint "29.2x30.35 Transformer")
      (description "Power Transformers MID-OLTI UCC28740 230 uH 60 W")
      (fields (field (name "MANUFACTURER") "Wurth Elektronik"))
      (libsource (lib "Symbols") (part "Switching Transformer"))
    )
    (comp (ref "T6")
      (value "750343068")
      (footprint "29.2x30.35 Transformer")
      (description "Power Transformers MID-OLTI UCC28740 230 uH 60 W")
      (fields (field (name "MANUFACTURER") "Wurth Elektronik"))
      (libsource (lib "Symbols") (part "Switching Transformer"))
    )
    (comp (ref "U1")
      (value "UCC2870DR")
      (footprint "SOIC-7")
      (description "170Hz~100kHz 9V~35V SOIC-7 AC-DC Controllers and Regulators ROHS")
      (fields (field (name "MANUFACTURER") "Texas Instruments") (field (name "MFR. PART #") "UCC28740DR"))
      (libsource (lib "Symbols") (part "UCC2870DR Flyback Controller"))
    )
    (comp (ref "U2")
      (value "TL431IDBVR")
      (footprint "SOT-23-5")
      (description "2.495V~36V ±2.2% 100mA Adjustable SOT-23-5 Voltage Reference ROHS")
      (fields (field (name "MANUFACTURER") "Texas Instruments"))
      (libsource (lib "Symbols") (part "Adjustable Voltage reference"))
    )
    (comp (ref "U3")
      (value "TL431IDBVR")
      (footprint "SOT-23-5")
      (description "2.495V~36V ±2.2% 100mA Adjustable SOT-23-5 Voltage Reference ROHS")
      (fields (field (name "MANUFACTURER") "Texas Instruments"))
      (libsource (lib "Symbols") (part "Adjustable Voltage reference"))
    )
    (comp (ref "U4")
      (value "TL431IDBVR")
      (footprint "SOT-23-5")
      (description "2.495V~36V ±2.2% 100mA Adjustable SOT-23-5 Voltage Reference ROHS")
      (fields (field (name "MANUFACTURER") "Texas Instruments"))
      (libsource (lib "Symbols") (part "Adjustable Voltage reference"))
    )
    (comp (ref "U5")
      (value "Optocoupler")
      (footprint "SMD-4P Optocoupler")
      (fields (field (name "MANUFACTURER") "TOSHIBA") (field (name "MFR. PART #") "TLP785(GB-TP6,F(C"))
      (libsource (lib "Symbols") (part "Optocoupler"))
    )
    (comp (ref "U6")
      (value "UCC2870DR")
      (footprint "SOIC-7")
      (description "170Hz~100kHz 9V~35V SOIC-7 AC-DC Controllers and Regulators ROHS")
      (fields (field (name "MANUFACTURER") "Texas Instruments") (field (name "MFR. PART #") "UCC28740DR"))
      (libsource (lib "Symbols") (part "UCC2870DR Flyback Controller"))
    )
    (comp (ref "U7")
      (value "UCC2870DR")
      (footprint "SOIC-7")
      (description "170Hz~100kHz 9V~35V SOIC-7 AC-DC Controllers and Regulators ROHS")
      (fields (field (name "MANUFACTURER") "Texas Instruments") (field (name "MFR. PART #") "UCC28740DR"))
      (libsource (lib "Symbols") (part "UCC2870DR Flyback Controller"))
    )
    (comp (ref "U8")
      (value "Optocoupler")
      (footprint "SMD-4P Optocoupler")
      (fields (field (name "MANUFACTURER") "TOSHIBA") (field (name "MFR. PART #") "TLP785(GB-TP6,F(C"))
      (libsource (lib "Symbols") (part "Optocoupler"))
    )
    (comp (ref "U9")
      (value "Optocoupler")
      (footprint "SMD-4P Optocoupler")
      (fields (field (name "MANUFACTURER") "TOSHIBA") (field (name "MFR. PART #") "TLP785(GB-TP6,F(C"))
      (libsource (lib "Symbols") (part "Optocoupler"))
    )
    (comp (ref "ZD1")
      (value "Zener Diode 120V")
      (footprint "SMB Zener diode")
      (description "Independent Type 114V~126V 3W 120V SMB Zener Diodes ROHS")
      (fields (field (name "MANUFACTURER") "LGE") (field (name "MFR. PART #") "3SMB5951B"))
      (libsource (lib "Symbols") (part "Zener Diode 120V"))
    )
    (comp (ref "ZD2")
      (value "Zener Diode 24V")
      (footprint "SMA(DO-214AC)")
      (description "Independent Type 22.8V~26V 1W 24V SMA(DO-214AC) Zener Diodes ROHS")
      (fields
        (field (name "MANUFACTURER") "MDD(Microdiode Semiconductor)")
        (field (name "MFR. PART #") "1SMA4749A")
      )
      (libsource (lib "Symbols") (part "Zener Diode 24V"))
    )
    (comp (ref "ZD3")
      (value "Zener Diode 120V")
      (footprint "SMB Zener diode")
      (description "Independent Type 114V~126V 3W 120V SMB Zener Diodes ROHS")
      (fields (field (name "MANUFACTURER") "LGE") (field (name "MFR. PART #") "3SMB5951B"))
      (libsource (lib "Symbols") (part "Zener Diode 120V"))
    )
    (comp (ref "ZD4")
      (value "Zener Diode 120V")
      (footprint "SMB Zener diode")
      (description "Independent Type 114V~126V 3W 120V SMB Zener Diodes ROHS")
      (fields (field (name "MANUFACTURER") "LGE") (field (name "MFR. PART #") "3SMB5951B"))
      (libsource (lib "Symbols") (part "Zener Diode 120V"))
    )
    (comp (ref "ZD5")
      (value "Zener Diode 24V")
      (footprint "SMA(DO-214AC)")
      (description "Independent Type 22.8V~26V 1W 24V SMA(DO-214AC) Zener Diodes ROHS")
      (fields
        (field (name "MANUFACTURER") "MDD(Microdiode Semiconductor)")
        (field (name "MFR. PART #") "1SMA4749A")
      )
      (libsource (lib "Symbols") (part "Zener Diode 24V"))
    )
    (comp (ref "ZD6")
      (value "Zener Diode 24V")
      (footprint "SMA(DO-214AC)")
      (description "Independent Type 22.8V~26V 1W 24V SMA(DO-214AC) Zener Diodes ROHS")
      (fields
        (field (name "MANUFACTURER") "MDD(Microdiode Semiconductor)")
        (field (name "MFR. PART #") "1SMA4749A")
      )
      (libsource (lib "Symbols") (part "Zener Diode 24V"))
    )
  )
  (nets
    (net (code "1") (name "/CS1") (class "Default")
      (node (ref "C40") (pin "1") (pinfunction "1_1") (pintype "passive"))
      (node (ref "R15") (pin "1") (pinfunction "1_1") (pintype "passive"))
      (node (ref "U1") (pin "5") (pinfunction "CS_5") (pintype "input"))
    )
    (net (code "2") (name "/CS2") (class "Default")
      (node (ref "C41") (pin "1") (pinfunction "1_1") (pintype "passive"))
      (node (ref "R24") (pin "1") (pinfunction "1_1") (pintype "passive"))
      (node (ref "U6") (pin "5") (pinfunction "CS_5") (pintype "input"))
    )
    (net (code "3") (name "/CS3") (class "Default")
      (node (ref "C42") (pin "1") (pinfunction "1_1") (pintype "passive"))
      (node (ref "R25") (pin "1") (pinfunction "1_1") (pintype "passive"))
      (node (ref "U7") (pin "5") (pinfunction "CS_5") (pintype "input"))
    )
    (net (code "4") (name "/DRV1") (class "Default")
      (node (ref "M1") (pin "1") (pinfunction "Gate_1") (pintype "passive"))
      (node (ref "U1") (pin "6") (pinfunction "DRV_6") (pintype "output"))
    )
    (net (code "5") (name "/DRV2") (class "Default")
      (node (ref "M2") (pin "1") (pinfunction "Gate_1") (pintype "passive"))
      (node (ref "U6") (pin "6") (pinfunction "DRV_6") (pintype "output"))
    )
    (net (code "6") (name "/DRV3") (class "Default")
      (node (ref "M3") (pin "1") (pinfunction "Gate_1") (pintype "passive"))
      (node (ref "U7") (pin "6") (pinfunction "DRV_6") (pintype "output"))
    )
    (net (code "7") (name "/FB1") (class "Default")
      (node (ref "C14") (pin "2") (pinfunction "2_2") (pintype "passive"))
      (node (ref "R17") (pin "1") (pinfunction "1_1") (pintype "passive"))
      (node (ref "R19") (pin "2") (pinfunction "2_2") (pintype "passive"))
      (node (ref "U1") (pin "3") (pinfunction "FB_3") (pintype "input"))
    )
    (net (code "8") (name "/FB2") (class "Default")
      (node (ref "C35") (pin "2") (pinfunction "2_2") (pintype "passive"))
      (node (ref "R28") (pin "1") (pinfunction "1_1") (pintype "passive"))
      (node (ref "R32") (pin "2") (pinfunction "2_2") (pintype "passive"))
      (node (ref "U6") (pin "3") (pinfunction "FB_3") (pintype "input"))
    )
    (net (code "9") (name "/FB3") (class "Default")
      (node (ref "C36") (pin "2") (pinfunction "2_2") (pintype "passive"))
      (node (ref "R29") (pin "1") (pinfunction "1_1") (pintype "passive"))
      (node (ref "R33") (pin "2") (pinfunction "2_2") (pintype "passive"))
      (node (ref "U7") (pin "3") (pinfunction "FB_3") (pintype "input"))
    )
    (net (code "10") (name "/SENSE1") (class "Default")
      (node (ref "M1") (pin "3") (pinfunction "Source_3") (pintype "passive"))
      (node (ref "R15") (pin "2") (pinfunction "2_2") (pintype "passive"))
      (node (ref "R18") (pin "2") (pinfunction "2_2") (pintype "passive"))
    )
    (net (code "11") (name "/SENSE2") (class "Default")
      (node (ref "M2") (pin "3") (pinfunction "Source_3") (pintype "passive"))
      (node (ref "R24") (pin "2") (pinfunction "2_2") (pintype "passive"))
      (node (ref "R30") (pin "2") (pinfunction "2_2") (pintype "passive"))
    )
    (net (code "12") (name "/SENSE3") (class "Default")
      (node (ref "M3") (pin "3") (pinfunction "Source_3") (pintype "passive"))
      (node (ref "R25") (pin "2") (pinfunction "2_2") (pintype "passive"))
      (node (ref "R31") (pin "2") (pinfunction "2_2") (pintype "passive"))
    )
    (net (code "13") (name "/SW1") (class "Default")
      (node (ref "D2") (pin "2") (pinfunction "Anode_2") (pintype "passive"))
      (node (ref "M1") (pin "2") (pinfunction "Drain_2") (pintype "passive"))
      (node (ref "T1") (pin "3") (pinfunction "3_3") (pintype "passive"))
      (node (ref "T2") (pin "3") (pinfunction "3_3") (pintype "passive"))
    )
    (net (code "14") (name "/SW2") (class "Default")
      (node (ref "D7") (pin "2") (pinfunction "Anode_2") (pintype "passive"))
      (node (ref "M2") (pin "2") (pinfunction "Drain_2") (pintype "passive"))
      (node (ref "T3") (pin "3") (pinfunction "3_3") (pintype "passive"))
      (node (ref "T5") (pin "3") (pinfunction "3_3") (pintype "passive"))
    )
    (net (code "15") (name "/SW3") (class "Default")
      (node (ref "D8") (pin "2") (pinfunction "Anode_2") (pintype "passive"))
      (node (ref "M3") (pin "2") (pinfunction "Drain_2") (pintype "passive"))
      (node (ref "T4") (pin "3") (pinfunction "3_3") (pintype "passive"))
      (node (ref "T6") (pin "3") (pinfunction "3_3") (pintype "passive"))
    )
    (net (code "16") (name "/VDD1") (class "Default")
      (node (ref "C13") (pin "1") (pinfunction "1_1") (pintype "passive"))
      (node (ref "D4") (pin "1") (pinfunction "Cathode_1") (pintype "passive"))
      (node (ref "U1") (pin "1") (pinfunction "VDD_1") (pintype "input"))
      (node (ref "U5") (pin "3") (pintype "passive"))
      (node (ref "ZD2") (pin "1") (pinfunction "Cathode_1") (pintype "passive"))
    )
    (net (code "17") (name "/VDD2") (class "Default")
      (node (ref "C33") (pin "1") (pinfunction "1_1") (pintype "passive"))
      (node (ref "D11") (pin "1") (pinfunction "Cathode_1") (pintype "passive"))
      (node (ref "U6") (pin "1") (pinfunction "VDD_1") (pintype "input"))
      (node (ref "U8") (pin "3") (pintype "passive"))
      (node (ref "ZD5") (pin "1") (pinfunction "Cathode_1") (pintype "passive"))
    )
    (net (code "18") (name "/VDD3") (class "Default")
      (node (ref "C34") (pin "1") (pinfunction "1_1") (pintype "passive"))
      (node (ref "D12") (pin "1") (pinfunction "Cathode_1") (pintype "passive"))
      (node (ref "U7") (pin "1") (pinfunction "VDD_1") (pintype "input"))
      (node (ref "U9") (pin "3") (pintype "passive"))
      (node (ref "ZD6") (pin "1") (pinfunction "Cathode_1") (pintype "passive"))
    )
    (net (code "19") (name "/VOUT1") (class "Default")
      (node (ref "R1") (pin "1") (pinfunction "1_1") (pintype "passive"))
      (node (ref "R9") (pin "2") (pinfunction "2_2") (pintype "passive"))
      (node (ref "U5") (pin "1") (pintype "passive"))
    )
    (net (code "20") (name "/VOUT2") (class "Default")
      (node (ref "R10") (pin "2") (pinfunction "2_2") (pintype "passive"))
      (node (ref "R2") (pin "1") (pinfunction "1_1") (pintype "passive"))
      (node (ref "U8") (pin "1") (pintype "passive"))
    )
    (net (code "21") (name "/VOUT3") (class "Default")
      (node (ref "R11") (pin "2") (pinfunction "2_2") (pintype "passive"))
      (node (ref "R3") (pin "1") (pinfunction "1_1") (pintype "passive"))
      (node (ref "U9") (pin "1") (pintype "passive"))
    )
    (net (code "22") (name "/VREF1") (class "Default")
      (node (ref "C37") (pin "1") (pinfunction "1_1") (pintype "passive"))
      (node (ref "R9") (pin "1") (pinfunction "1_1") (pintype "passive"))
      (node (ref "U2") (pin "3") (pinfunction "K_3") (pintype "passive"))
      (node (ref "U5") (pin "2") (pintype "passive"))
    )
    (net (code "23") (name "/VREF2") (class "Default")
      (node (ref "C38") (pin "2") (pinfunction "2_2") (pintype "passive"))
      (node (ref "R10") (pin "1") (pinfunction "1_1") (pintype "passive"))
      (node (ref "U3") (pin "3") (pinfunction "K_3") (pintype "passive"))
      (node (ref "U8") (pin "2") (pintype "passive"))
    )
    (net (code "24") (name "/VREF3") (class "Default")
      (node (ref "C39") (pin "2") (pinfunction "2_2") (pintype "passive"))
      (node (ref "R11") (pin "1") (pinfunction "1_1") (pintype "passive"))
      (node (ref "U4") (pin "3") (pinfunction "K_3") (pintype "passive"))
      (node (ref "U9") (pin "2") (pintype "passive"))
    )
    (net (code "25") (name "/VS1") (class "Default")
      (node (ref "R16") (pin "2") (pinfunction "2_2") (pintype "passive"))
      (node (ref "R8") (pin "1") (pinfunction "1_1") (pintype "passive"))
      (node (ref "U1") (pin "2") (pinfunction "VS_2") (pintype "input"))
    )
    (net (code "26") (name "/VS2") (class "Default")
      (node (ref "R21") (pin "1") (pinfunction "1_1") (pintype "passive"))
      (node (ref "R26") (pin "2") (pinfunction "2_2") (pintype "passive"))
      (node (ref "U6") (pin "2") (pinfunction "VS_2") (pintype "input"))
    )
    (net (code "27") (name "/VS3") (class "Default")
      (node (ref "R23") (pin "1") (pinfunction "1_1") (pintype "passive"))
      (node (ref "R27") (pin "2") (pinfunction "2_2") (pintype "passive"))
      (node (ref "U7") (pin "2") (pinfunction "VS_2") (pintype "input"))
    )
    (net (code "28") (name "25V_1") (class "Default")
      (node (ref "C1") (pin "1") (pinfunction "1_1") (pintype "passive"))
      (node (ref "C3") (pin "2") (pinfunction "2_2") (pintype "passive"))
      (node (ref "C4") (pin "2") (pinfunction "2_2") (pintype "passive"))
      (node (ref "C5") (pin "2") (pinfunction "2_2") (pintype "passive"))
      (node (ref "C6") (pin "2") (pinfunction "2_2") (pintype "passive"))
      (node (ref "D1") (pin "1") (pinfunction "Cathode_1") (pintype "passive"))
      (node (ref "J3") (pin "1") (pinfunction "1_1") (pintype "passive"))
      (node (ref "R1") (pin "2") (pinfunction "2_2") (pintype "passive"))
      (node (ref "R34") (pin "2") (pinfunction "2_2") (pintype "passive"))
      (node (ref "R4") (pin "2") (pinfunction "2_2") (pintype "passive"))
    )
    (net (code "29") (name "25V_2") (class "Default")
      (node (ref "C10") (pin "2") (pinfunction "2_2") (pintype "passive"))
      (node (ref "C11") (pin "2") (pinfunction "2_2") (pintype "passive"))
      (node (ref "C12") (pin "2") (pinfunction "2_2") (pintype "passive"))
      (node (ref "C2") (pin "1") (pinfunction "1_1") (pintype "passive"))
      (node (ref "C9") (pin "2") (pinfunction "2_2") (pintype "passive"))
      (node (ref "D3") (pin "1") (pinfunction "Cathode_1") (pintype "passive"))
      (node (ref "J4") (pin "1") (pinfunction "1_1") (pintype "passive"))
      (node (ref "R35") (pin "2") (pinfunction "2_2") (pintype "passive"))
    )
    (net (code "30") (name "25V_3") (class "Default")
      (node (ref "C17") (pin "2") (pinfunction "2_2") (pintype "passive"))
      (node (ref "C18") (pin "2") (pinfunction "2_2") (pintype "passive"))
      (node (ref "C19") (pin "2") (pinfunction "2_2") (pintype "passive"))
      (node (ref "C20") (pin "2") (pinfunction "2_2") (pintype "passive"))
      (node (ref "C7") (pin "1") (pinfunction "1_1") (pintype "passive"))
      (node (ref "D5") (pin "1") (pinfunction "Cathode_1") (pintype "passive"))
      (node (ref "J5") (pin "1") (pinfunction "1_1") (pintype "passive"))
      (node (ref "R2") (pin "2") (pinfunction "2_2") (pintype "passive"))
      (node (ref "R36") (pin "2") (pinfunction "2_2") (pintype "passive"))
      (node (ref "R5") (pin "2") (pinfunction "2_2") (pintype "passive"))
    )
    (net (code "31") (name "25V_4") (class "Default")
      (node (ref "C25") (pin "2") (pinfunction "2_2") (pintype "passive"))
      (node (ref "C26") (pin "2") (pinfunction "2_2") (pintype "passive"))
      (node (ref "C27") (pin "2") (pinfunction "2_2") (pintype "passive"))
      (node (ref "C28") (pin "2") (pinfunction "2_2") (pintype "passive"))
      (node (ref "C8") (pin "1") (pinfunction "1_1") (pintype "passive"))
      (node (ref "D9") (pin "1") (pinfunction "Cathode_1") (pintype "passive"))
      (node (ref "J6") (pin "1") (pinfunction "1_1") (pintype "passive"))
      (node (ref "R37") (pin "2") (pinfunction "2_2") (pintype "passive"))
    )
    (net (code "32") (name "25V_5") (class "Default")
      (node (ref "C15") (pin "1") (pinfunction "1_1") (pintype "passive"))
      (node (ref "C21") (pin "2") (pinfunction "2_2") (pintype "passive"))
      (node (ref "C22") (pin "2") (pinfunction "2_2") (pintype "passive"))
      (node (ref "C23") (pin "2") (pinfunction "2_2") (pintype "passive"))
      (node (ref "C24") (pin "2") (pinfunction "2_2") (pintype "passive"))
      (node (ref "D6") (pin "1") (pinfunction "Cathode_1") (pintype "passive"))
      (node (ref "J7") (pin "1") (pinfunction "1_1") (pintype "passive"))
      (node (ref "R3") (pin "2") (pinfunction "2_2") (pintype "passive"))
      (node (ref "R38") (pin "2") (pinfunction "2_2") (pintype "passive"))
      (node (ref "R6") (pin "2") (pinfunction "2_2") (pintype "passive"))
    )
    (net (code "33") (name "25V_6") (class "Default")
      (node (ref "C16") (pin "1") (pinfunction "1_1") (pintype "passive"))
      (node (ref "C29") (pin "2") (pinfunction "2_2") (pintype "passive"))
      (node (ref "C30") (pin "2") (pinfunction "2_2") (pintype "passive"))
      (node (ref "C31") (pin "2") (pinfunction "2_2") (pintype "passive"))
      (node (ref "C32") (pin "2") (pinfunction "2_2") (pintype "passive"))
      (node (ref "D10") (pin "1") (pinfunction "Cathode_1") (pintype "passive"))
      (node (ref "J8") (pin "1") (pinfunction "1_1") (pintype "passive"))
      (node (ref "R39") (pin "2") (pinfunction "2_2") (pintype "passive"))
    )
    (net (code "34") (name "GND") (class "Default")
      (node (ref "C13") (pin "2") (pinfunction "2_2") (pintype "passive"))
      (node (ref "C33") (pin "2") (pinfunction "2_2") (pintype "passive"))
      (node (ref "C34") (pin "2") (pinfunction "2_2") (pintype "passive"))
      (node (ref "C40") (pin "2") (pinfunction "2_2") (pintype "passive"))
      (node (ref "C41") (pin "2") (pinfunction "2_2") (pintype "passive"))
      (node (ref "C42") (pin "2") (pinfunction "2_2") (pintype "passive"))
      (node (ref "J2") (pin "1") (pinfunction "1_1") (pintype "passive"))
      (node (ref "R16") (pin "1") (pinfunction "1_1") (pintype "passive"))
      (node (ref "R18") (pin "1") (pinfunction "1_1") (pintype "passive"))
      (node (ref "R19") (pin "1") (pinfunction "1_1") (pintype "passive"))
      (node (ref "R26") (pin "1") (pinfunction "1_1") (pintype "passive"))
      (node (ref "R27") (pin "1") (pinfunction "1_1") (pintype "passive"))
      (node (ref "R30") (pin "1") (pinfunction "1_1") (pintype "passive"))
      (node (ref "R31") (pin "1") (pinfunction "1_1") (pintype "passive"))
      (node (ref "R32") (pin "1") (pinfunction "1_1") (pintype "passive"))
      (node (ref "R33") (pin "1") (pinfunction "1_1") (pintype "passive"))
      (node (ref "T1") (pin "6") (pinfunction "6_6") (pintype "passive"))
      (node (ref "T3") (pin "6") (pinfunction "6_6") (pintype "passive"))
      (node (ref "T4") (pin "6") (pinfunction "6_6") (pintype "passive"))
      (node (ref "U1") (pin "4") (pinfunction "GND_4") (pintype "power_in"))
      (node (ref "U6") (pin "4") (pinfunction "GND_4") (pintype "power_in"))
      (node (ref "U7") (pin "4") (pinfunction "GND_4") (pintype "power_in"))
      (node (ref "ZD2") (pin "2") (pinfunction "Anode_2") (pintype "passive"))
      (node (ref "ZD5") (pin "2") (pinfunction "Anode_2") (pintype "passive"))
      (node (ref "ZD6") (pin "2") (pinfunction "Anode_2") (pintype "passive"))
    )
    (net (code "35") (name "GND1") (class "Default")
      (node (ref "C1") (pin "2") (pinfunction "2_2") (pintype "passive"))
      (node (ref "C3") (pin "1") (pinfunction "1_1") (pintype "passive"))
      (node (ref "C4") (pin "1") (pinfunction "1_1") (pintype "passive"))
      (node (ref "C5") (pin "1") (pinfunction "1_1") (pintype "passive"))
      (node (ref "C6") (pin "1") (pinfunction "1_1") (pintype "passive"))
      (node (ref "D13") (pin "2") (pinfunction "2_2") (pintype "passive"))
      (node (ref "J3") (pin "2") (pinfunction "2_2") (pintype "passive"))
      (node (ref "R12") (pin "1") (pinfunction "1_1") (pintype "passive"))
      (node (ref "T1") (pin "10") (pinfunction "10_10") (pintype "passive"))
      (node (ref "U2") (pin "5") (pinfunction "A_5") (pintype "passive"))
    )
    (net (code "36") (name "GND2") (class "Default")
      (node (ref "C10") (pin "1") (pinfunction "1_1") (pintype "passive"))
      (node (ref "C11") (pin "1") (pinfunction "1_1") (pintype "passive"))
      (node (ref "C12") (pin "1") (pinfunction "1_1") (pintype "passive"))
      (node (ref "C2") (pin "2") (pinfunction "2_2") (pintype "passive"))
      (node (ref "C9") (pin "1") (pinfunction "1_1") (pintype "passive"))
      (node (ref "D14") (pin "2") (pinfunction "2_2") (pintype "passive"))
      (node (ref "J4") (pin "2") (pinfunction "2_2") (pintype "passive"))
      (node (ref "T2") (pin "10") (pinfunction "10_10") (pintype "passive"))
    )
    (net (code "37") (name "GND3") (class "Default")
      (node (ref "C17") (pin "1") (pinfunction "1_1") (pintype "passive"))
      (node (ref "C18") (pin "1") (pinfunction "1_1") (pintype "passive"))
      (node (ref "C19") (pin "1") (pinfunction "1_1") (pintype "passive"))
      (node (ref "C20") (pin "1") (pinfunction "1_1") (pintype "passive"))
      (node (ref "C7") (pin "2") (pinfunction "2_2") (pintype "passive"))
      (node (ref "D15") (pin "2") (pinfunction "2_2") (pintype "passive"))
      (node (ref "J5") (pin "2") (pinfunction "2_2") (pintype "passive"))
      (node (ref "R13") (pin "1") (pinfunction "1_1") (pintype "passive"))
      (node (ref "T3") (pin "10") (pinfunction "10_10") (pintype "passive"))
      (node (ref "U3") (pin "5") (pinfunction "A_5") (pintype "passive"))
    )
    (net (code "38") (name "GND4") (class "Default")
      (node (ref "C25") (pin "1") (pinfunction "1_1") (pintype "passive"))
      (node (ref "C26") (pin "1") (pinfunction "1_1") (pintype "passive"))
      (node (ref "C27") (pin "1") (pinfunction "1_1") (pintype "passive"))
      (node (ref "C28") (pin "1") (pinfunction "1_1") (pintype "passive"))
      (node (ref "C8") (pin "2") (pinfunction "2_2") (pintype "passive"))
      (node (ref "D16") (pin "2") (pinfunction "2_2") (pintype "passive"))
      (node (ref "J6") (pin "2") (pinfunction "2_2") (pintype "passive"))
      (node (ref "T5") (pin "10") (pinfunction "10_10") (pintype "passive"))
    )
    (net (code "39") (name "GND5") (class "Default")
      (node (ref "C15") (pin "2") (pinfunction "2_2") (pintype "passive"))
      (node (ref "C21") (pin "1") (pinfunction "1_1") (pintype "passive"))
      (node (ref "C22") (pin "1") (pinfunction "1_1") (pintype "passive"))
      (node (ref "C23") (pin "1") (pinfunction "1_1") (pintype "passive"))
      (node (ref "C24") (pin "1") (pinfunction "1_1") (pintype "passive"))
      (node (ref "D17") (pin "2") (pinfunction "2_2") (pintype "passive"))
      (node (ref "J7") (pin "2") (pinfunction "2_2") (pintype "passive"))
      (node (ref "R14") (pin "1") (pinfunction "1_1") (pintype "passive"))
      (node (ref "T4") (pin "10") (pinfunction "10_10") (pintype "passive"))
      (node (ref "U4") (pin "5") (pinfunction "A_5") (pintype "passive"))
    )
    (net (code "40") (name "GND6") (class "Default")
      (node (ref "C16") (pin "2") (pinfunction "2_2") (pintype "passive"))
      (node (ref "C29") (pin "1") (pinfunction "1_1") (pintype "passive"))
      (node (ref "C30") (pin "1") (pinfunction "1_1") (pintype "passive"))
      (node (ref "C31") (pin "1") (pinfunction "1_1") (pintype "passive"))
      (node (ref "C32") (pin "1") (pinfunction "1_1") (pintype "passive"))
      (node (ref "D18") (pin "2") (pinfunction "2_2") (pintype "passive"))
      (node (ref "J8") (pin "2") (pinfunction "2_2") (pintype "passive"))
      (node (ref "T6") (pin "10") (pinfunction "10_10") (pintype "passive"))
    )
    (net (code "41") (name "Net-(C14-Pad1)") (class "Default")
      (node (ref "C14") (pin "1") (pinfunction "1_1") (pintype "passive"))
      (node (ref "R17") (pin "2") (pinfunction "2_2") (pintype "passive"))
      (node (ref "U5") (pin "4") (pintype "passive"))
    )
    (net (code "42") (name "Net-(C35-Pad1)") (class "Default")
      (node (ref "C35") (pin "1") (pinfunction "1_1") (pintype "passive"))
      (node (ref "R28") (pin "2") (pinfunction "2_2") (pintype "passive"))
      (node (ref "U8") (pin "4") (pintype "passive"))
    )
    (net (code "43") (name "Net-(C36-Pad1)") (class "Default")
      (node (ref "C36") (pin "1") (pinfunction "1_1") (pintype "passive"))
      (node (ref "R29") (pin "2") (pinfunction "2_2") (pintype "passive"))
      (node (ref "U9") (pin "4") (pintype "passive"))
    )
    (net (code "44") (name "Net-(D1-Anode)") (class "Default")
      (node (ref "D1") (pin "2") (pinfunction "Anode_2") (pintype "passive"))
      (node (ref "T1") (pin "12") (pinfunction "12_12") (pintype "passive"))
    )
    (net (code "45") (name "Net-(D2-Cathode)") (class "Default")
      (node (ref "D2") (pin "1") (pinfunction "Cathode_1") (pintype "passive"))
      (node (ref "ZD1") (pin "1") (pinfunction "Cathode_1") (pintype "passive"))
    )
    (net (code "46") (name "Net-(D3-Anode)") (class "Default")
      (node (ref "D3") (pin "2") (pinfunction "Anode_2") (pintype "passive"))
      (node (ref "T2") (pin "12") (pinfunction "12_12") (pintype "passive"))
    )
    (net (code "47") (name "Net-(D4-Anode)") (class "Default")
      (node (ref "D4") (pin "2") (pinfunction "Anode_2") (pintype "passive"))
      (node (ref "R7") (pin "1") (pinfunction "1_1") (pintype "passive"))
    )
    (net (code "48") (name "Net-(D5-Anode)") (class "Default")
      (node (ref "D5") (pin "2") (pinfunction "Anode_2") (pintype "passive"))
      (node (ref "T3") (pin "12") (pinfunction "12_12") (pintype "passive"))
    )
    (net (code "49") (name "Net-(D6-Anode)") (class "Default")
      (node (ref "D6") (pin "2") (pinfunction "Anode_2") (pintype "passive"))
      (node (ref "T4") (pin "12") (pinfunction "12_12") (pintype "passive"))
    )
    (net (code "50") (name "Net-(D7-Cathode)") (class "Default")
      (node (ref "D7") (pin "1") (pinfunction "Cathode_1") (pintype "passive"))
      (node (ref "ZD3") (pin "1") (pinfunction "Cathode_1") (pintype "passive"))
    )
    (net (code "51") (name "Net-(D8-Cathode)") (class "Default")
      (node (ref "D8") (pin "1") (pinfunction "Cathode_1") (pintype "passive"))
      (node (ref "ZD4") (pin "1") (pinfunction "Cathode_1") (pintype "passive"))
    )
    (net (code "52") (name "Net-(D9-Anode)") (class "Default")
      (node (ref "D9") (pin "2") (pinfunction "Anode_2") (pintype "passive"))
      (node (ref "T5") (pin "12") (pinfunction "12_12") (pintype "passive"))
    )
    (net (code "53") (name "Net-(D10-Anode)") (class "Default")
      (node (ref "D10") (pin "2") (pinfunction "Anode_2") (pintype "passive"))
      (node (ref "T6") (pin "12") (pinfunction "12_12") (pintype "passive"))
    )
    (net (code "54") (name "Net-(D11-Anode)") (class "Default")
      (node (ref "D11") (pin "2") (pinfunction "Anode_2") (pintype "passive"))
      (node (ref "R20") (pin "1") (pinfunction "1_1") (pintype "passive"))
    )
    (net (code "55") (name "Net-(D12-Anode)") (class "Default")
      (node (ref "D12") (pin "2") (pinfunction "Anode_2") (pintype "passive"))
      (node (ref "R22") (pin "1") (pinfunction "1_1") (pintype "passive"))
    )
    (net (code "56") (name "Net-(D13-Pad1)") (class "Default")
      (node (ref "D13") (pin "1") (pinfunction "1_1") (pintype "passive"))
      (node (ref "R34") (pin "1") (pinfunction "1_1") (pintype "passive"))
    )
    (net (code "57") (name "Net-(D14-Pad1)") (class "Default")
      (node (ref "D14") (pin "1") (pinfunction "1_1") (pintype "passive"))
      (node (ref "R35") (pin "1") (pinfunction "1_1") (pintype "passive"))
    )
    (net (code "58") (name "Net-(D15-Pad1)") (class "Default")
      (node (ref "D15") (pin "1") (pinfunction "1_1") (pintype "passive"))
      (node (ref "R36") (pin "1") (pinfunction "1_1") (pintype "passive"))
    )
    (net (code "59") (name "Net-(D16-Pad1)") (class "Default")
      (node (ref "D16") (pin "1") (pinfunction "1_1") (pintype "passive"))
      (node (ref "R37") (pin "1") (pinfunction "1_1") (pintype "passive"))
    )
    (net (code "60") (name "Net-(D17-Pad1)") (class "Default")
      (node (ref "D17") (pin "1") (pinfunction "1_1") (pintype "passive"))
      (node (ref "R38") (pin "1") (pinfunction "1_1") (pintype "passive"))
    )
    (net (code "61") (name "Net-(D18-Pad1)") (class "Default")
      (node (ref "D18") (pin "1") (pinfunction "1_1") (pintype "passive"))
      (node (ref "R39") (pin "1") (pinfunction "1_1") (pintype "passive"))
    )
    (net (code "62") (name "Net-(R7-Pad2)") (class "Default")
      (node (ref "R7") (pin "2") (pinfunction "2_2") (pintype "passive"))
      (node (ref "R8") (pin "2") (pinfunction "2_2") (pintype "passive"))
      (node (ref "T1") (pin "7") (pinfunction "7_7") (pintype "passive"))
    )
    (net (code "63") (name "Net-(R20-Pad2)") (class "Default")
      (node (ref "R20") (pin "2") (pinfunction "2_2") (pintype "passive"))
      (node (ref "R21") (pin "2") (pinfunction "2_2") (pintype "passive"))
      (node (ref "T3") (pin "7") (pinfunction "7_7") (pintype "passive"))
    )
    (net (code "64") (name "Net-(R22-Pad2)") (class "Default")
      (node (ref "R22") (pin "2") (pinfunction "2_2") (pintype "passive"))
      (node (ref "R23") (pin "2") (pinfunction "2_2") (pintype "passive"))
      (node (ref "T4") (pin "7") (pinfunction "7_7") (pintype "passive"))
    )
    (net (code "65") (name "Net-(U2-REF)") (class "Default")
      (node (ref "C37") (pin "2") (pinfunction "2_2") (pintype "passive"))
      (node (ref "R12") (pin "2") (pinfunction "2_2") (pintype "passive"))
      (node (ref "R4") (pin "1") (pinfunction "1_1") (pintype "passive"))
      (node (ref "U2") (pin "4") (pinfunction "REF_4") (pintype "passive"))
    )
    (net (code "66") (name "Net-(U3-REF)") (class "Default")
      (node (ref "C38") (pin "1") (pinfunction "1_1") (pintype "passive"))
      (node (ref "R13") (pin "2") (pinfunction "2_2") (pintype "passive"))
      (node (ref "R5") (pin "1") (pinfunction "1_1") (pintype "passive"))
      (node (ref "U3") (pin "4") (pinfunction "REF_4") (pintype "passive"))
    )
    (net (code "67") (name "Net-(U4-REF)") (class "Default")
      (node (ref "C39") (pin "1") (pinfunction "1_1") (pintype "passive"))
      (node (ref "R14") (pin "2") (pinfunction "2_2") (pintype "passive"))
      (node (ref "R6") (pin "1") (pinfunction "1_1") (pintype "passive"))
      (node (ref "U4") (pin "4") (pinfunction "REF_4") (pintype "passive"))
    )
    (net (code "68") (name "VIN") (class "Default")
      (node (ref "J1") (pin "1") (pinfunction "1_1") (pintype "passive"))
      (node (ref "T1") (pin "1") (pinfunction "1_1") (pintype "passive"))
      (node (ref "T2") (pin "1") (pinfunction "1_1") (pintype "passive"))
      (node (ref "T3") (pin "1") (pinfunction "1_1") (pintype "passive"))
      (node (ref "T4") (pin "1") (pinfunction "1_1") (pintype "passive"))
      (node (ref "T5") (pin "1") (pinfunction "1_1") (pintype "passive"))
      (node (ref "T6") (pin "1") (pinfunction "1_1") (pintype "passive"))
      (node (ref "U1") (pin "7") (pinfunction "HV_7") (pintype "input"))
      (node (ref "U6") (pin "7") (pinfunction "HV_7") (pintype "input"))
      (node (ref "U7") (pin "7") (pinfunction "HV_7") (pintype "input"))
      (node (ref "ZD1") (pin "2") (pinfunction "Anode_2") (pintype "passive"))
      (node (ref "ZD3") (pin "2") (pinfunction "Anode_2") (pintype "passive"))
      (node (ref "ZD4") (pin "2") (pinfunction "Anode_2") (pintype "passive"))
    )
    (net (code "69") (name "unconnected-(H1-Pad1)") (class "Default")
      (node (ref "H1") (pin "1") (pinfunction "1_1") (pintype "passive+no_connect"))
    )
    (net (code "70") (name "unconnected-(H2-Pad1)") (class "Default")
      (node (ref "H2") (pin "1") (pinfunction "1_1") (pintype "passive+no_connect"))
    )
    (net (code "71") (name "unconnected-(H3-Pad1)") (class "Default")
      (node (ref "H3") (pin "1") (pinfunction "1_1") (pintype "passive+no_connect"))
    )
    (net (code "72") (name "unconnected-(H4-Pad1)") (class "Default")
      (node (ref "H4") (pin "1") (pinfunction "1_1") (pintype "passive+no_connect"))
    )
    (net (code "73") (name "unconnected-(T1-Pad2)") (class "Default")
      (node (ref "T1") (pin "2") (pinfunction "2_2") (pintype "passive+no_connect"))
    )
    (net (code "74") (name "unconnected-(T2-Pad2)") (class "Default")
      (node (ref "T2") (pin "2") (pinfunction "2_2") (pintype "passive+no_connect"))
    )
    (net (code "75") (name "unconnected-(T2-Pad6)") (class "Default")
      (node (ref "T2") (pin "6") (pinfunction "6_6") (pintype "passive+no_connect"))
    )
    (net (code "76") (name "unconnected-(T2-Pad7)") (class "Default")
      (node (ref "T2") (pin "7") (pinfunction "7_7") (pintype "passive+no_connect"))
    )
    (net (code "77") (name "unconnected-(T3-Pad2)") (class "Default")
      (node (ref "T3") (pin "2") (pinfunction "2_2") (pintype "passive+no_connect"))
    )
    (net (code "78") (name "unconnected-(T4-Pad2)") (class "Default")
      (node (ref "T4") (pin "2") (pinfunction "2_2") (pintype "passive+no_connect"))
    )
    (net (code "79") (name "unconnected-(T5-Pad2)") (class "Default")
      (node (ref "T5") (pin "2") (pinfunction "2_2") (pintype "passive+no_connect"))
    )
    (net (code "80") (name "unconnected-(T5-Pad6)") (class "Default")
      (node (ref "T5") (pin "6") (pinfunction "6_6") (pintype "passive+no_connect"))
    )
    (net (code "81") (name "unconnected-(T5-Pad7)") (class "Default")
      (node (ref "T5") (pin "7") (pinfunction "7_7") (pintype "passive+no_connect"))
    )
    (net (code "82") (name "unconnected-(T6-Pad2)") (class "Default")
      (node (ref "T6") (pin "2") (pinfunction "2_2") (pintype "passive+no_connect"))
    )
    (net (code "83") (name "unconnected-(T6-Pad6)") (class "Default")
      (node (ref "T6") (pin "6") (pinfunction "6_6") (pintype "passive+no_connect"))
    )
    (net (code "84") (name "unconnected-(T6-Pad7)") (class "Default")
      (node (ref "T6") (pin "7") (pinfunction "7_7") (pintype "passive+no_connect"))
    )
    (net (code "85") (name "unconnected-(U2-NC-Pad1)") (class "Default")
      (node (ref "U2") (pin "1") (pinfunction "NC_1") (pintype "passive+no_connect"))
    )
    (net (code "86") (name "unconnected-(U3-NC-Pad1)") (class "Default")
      (node (ref "U3") (pin "1") (pinfunction "NC_1") (pintype "passive+no_connect"))
    )
    (net (code "87") (name "unconnected-(U4-NC-Pad1)") (class "Default")
      (node (ref "U4") (pin "1") (pinfunction "NC_1") (pintype "passive+no_connect"))
    )
  )
)
